# M8650D_vrs.net
KiCad netlist of a schematic drawn in EAGLE
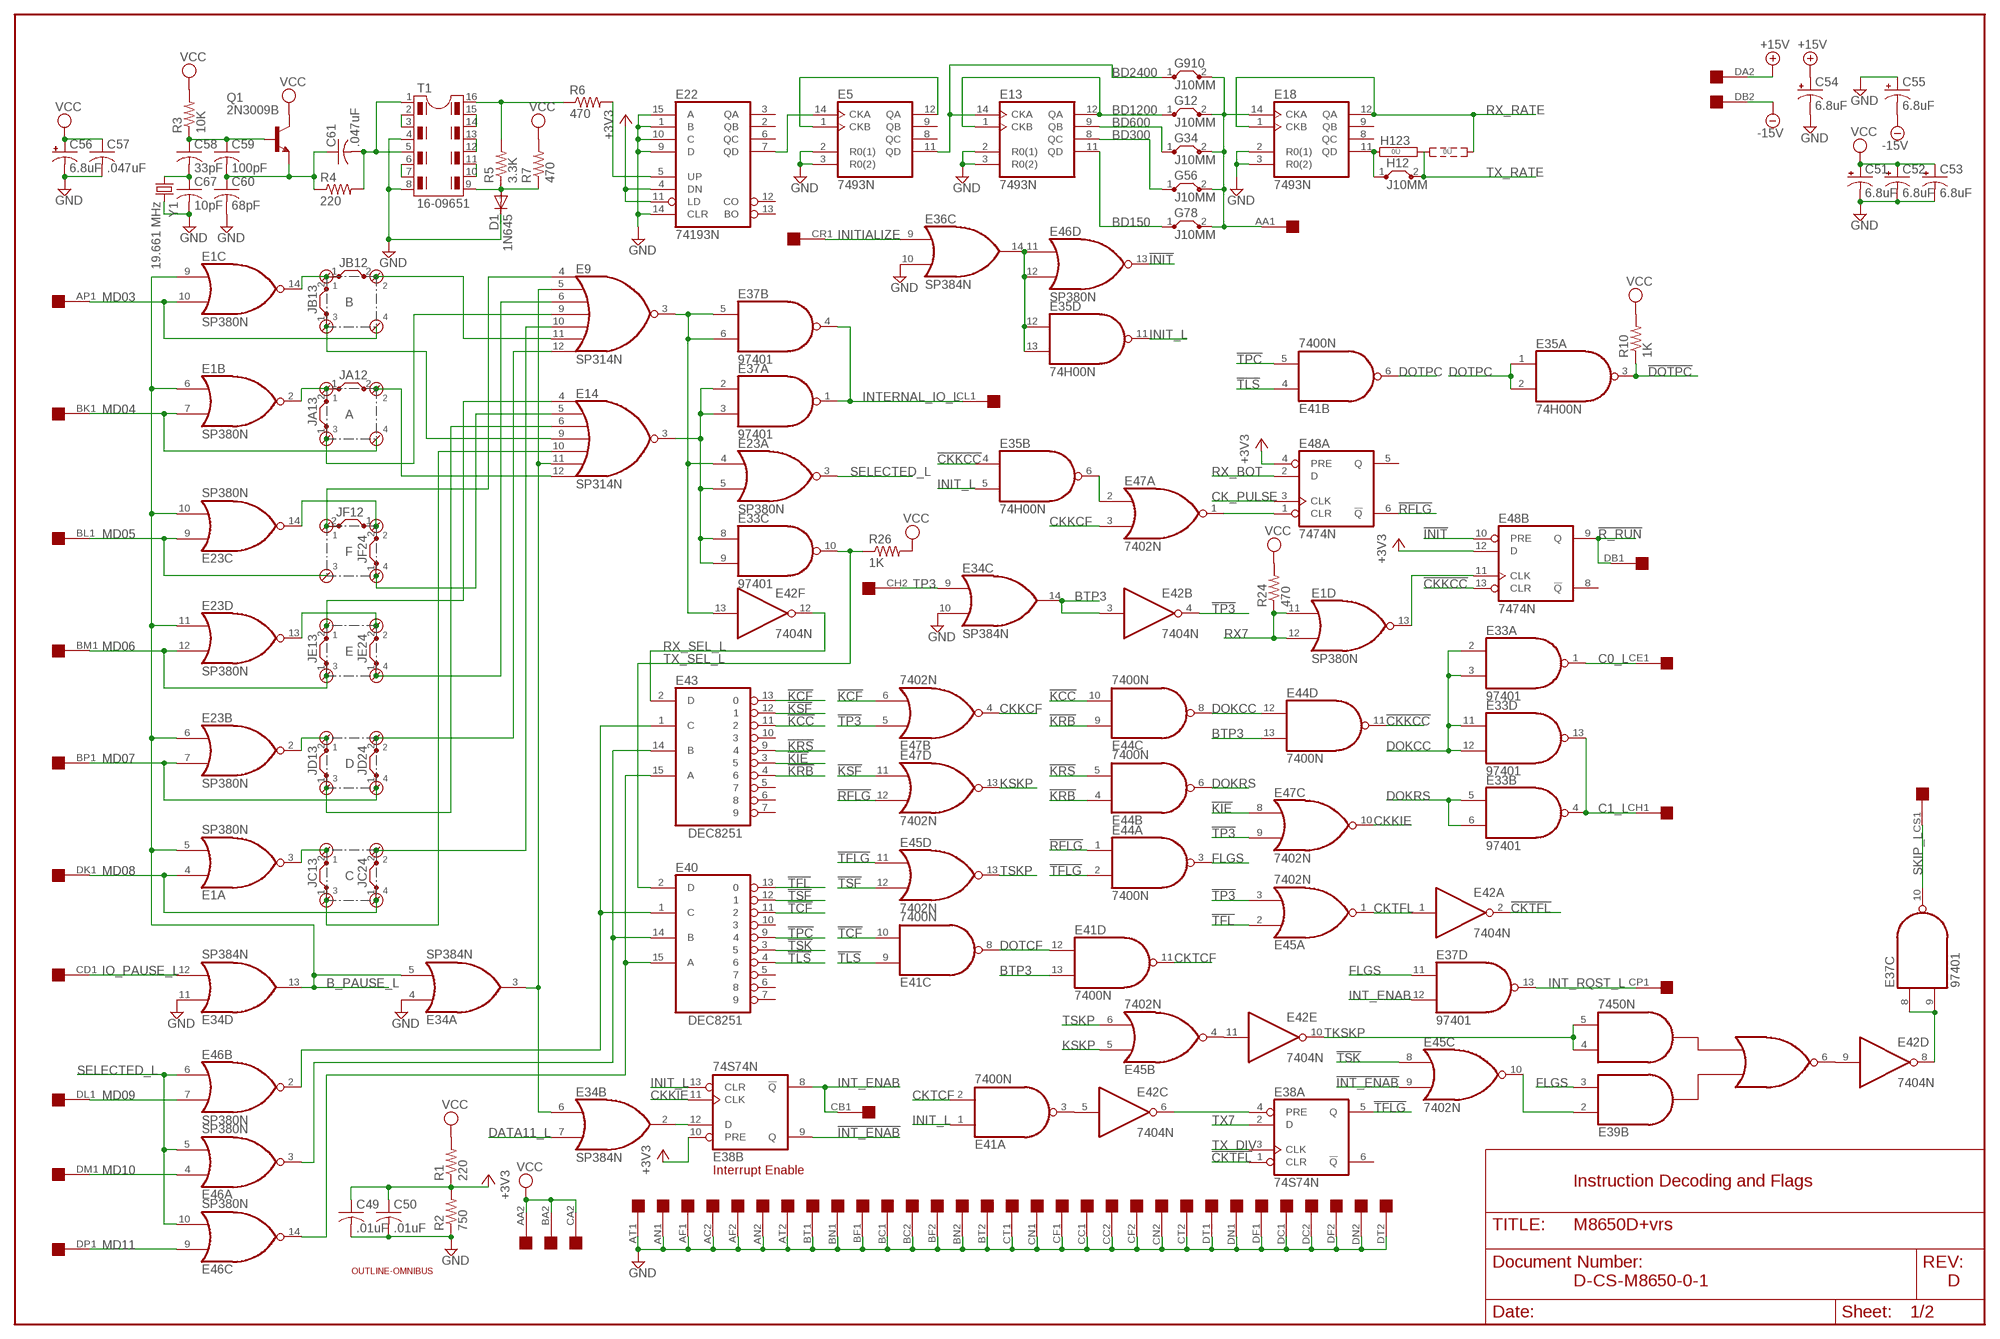
[diagram p0: schematic, sheet 1]
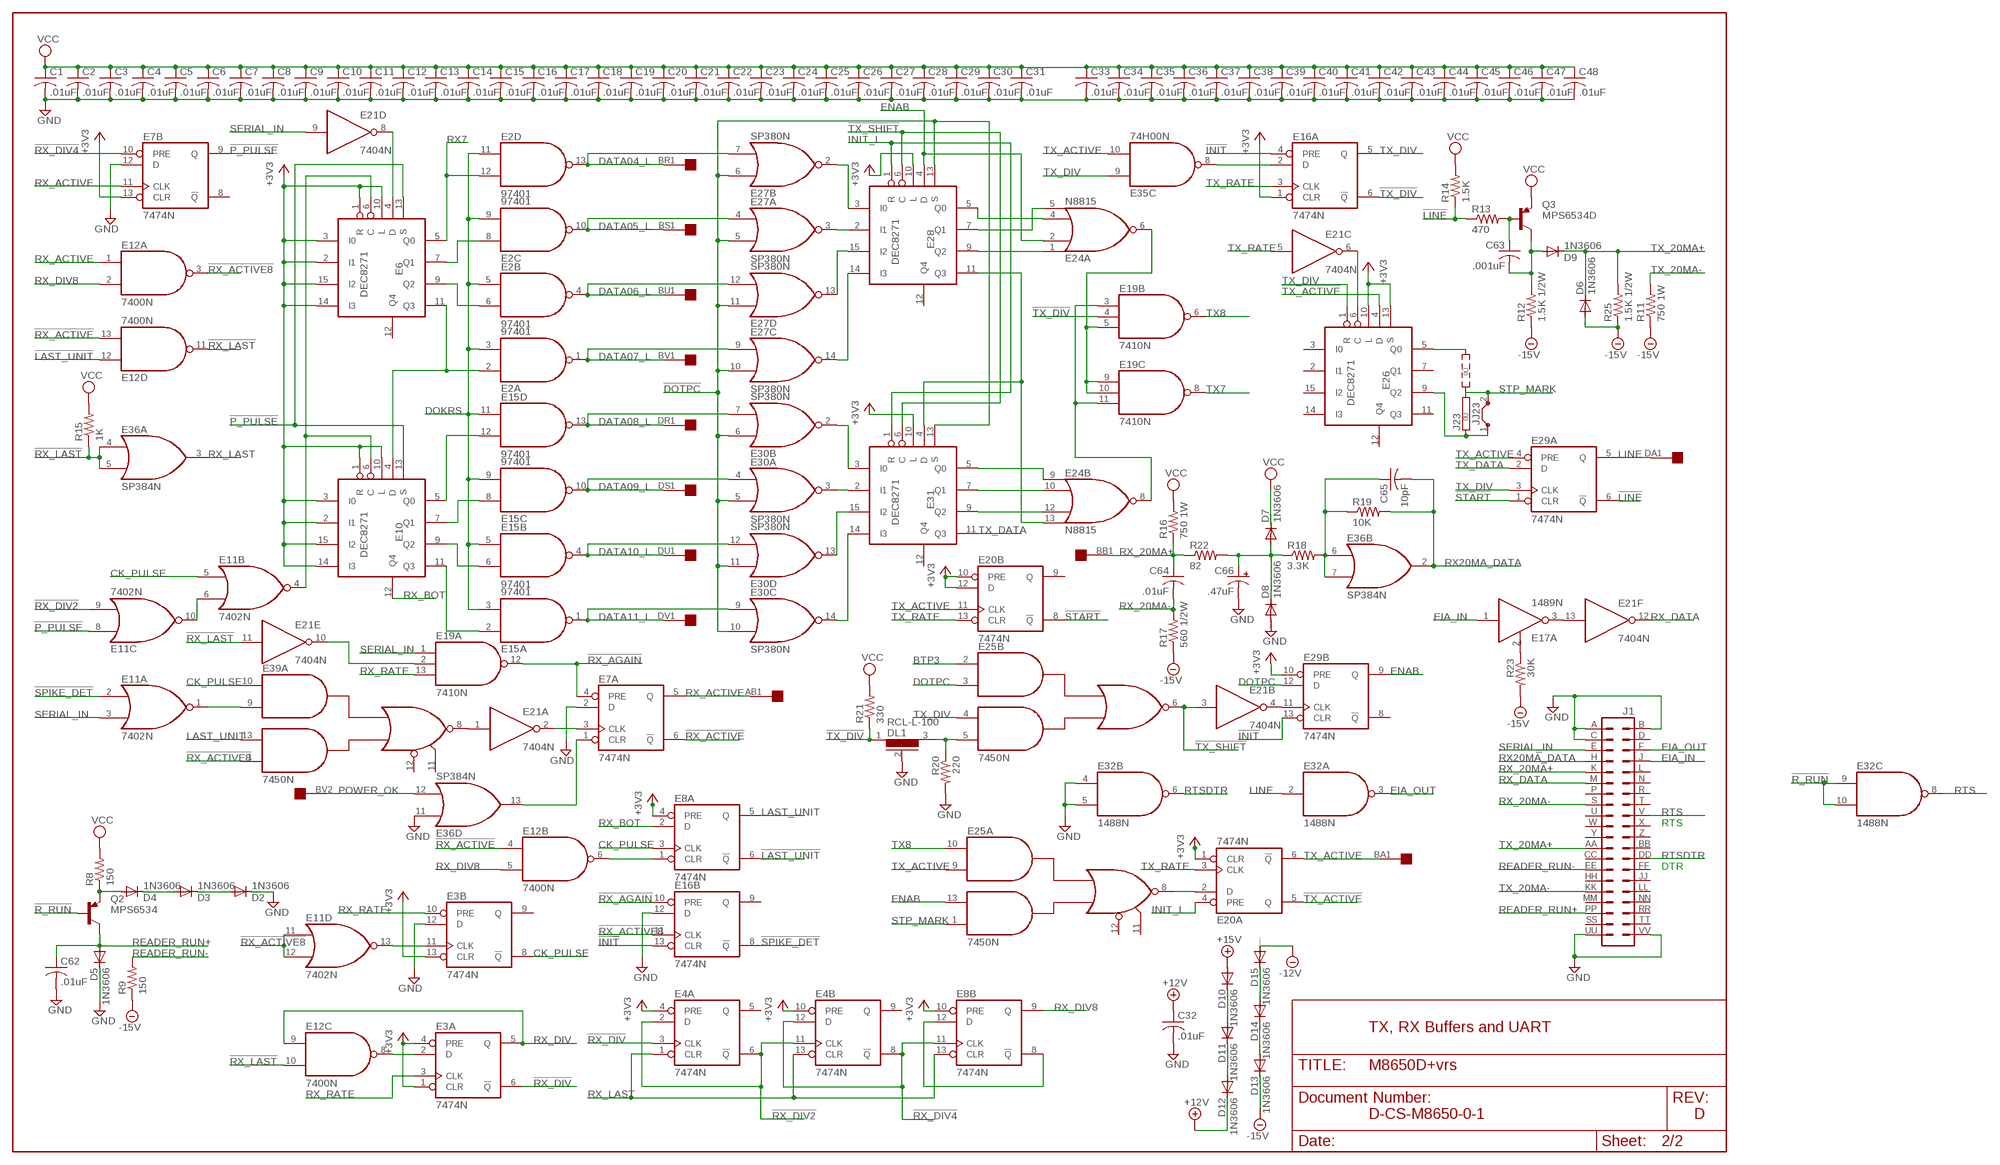
[diagram p1: schematic, sheet 2]

(export (version "E")
  (design (tool "Eeschema 10.0.6"))
  (components
    (comp (ref "C1")
      (value ".01uF")
      (footprint "eagle-import:C050-025X075")
      (libsource (lib "eagle-import") (part "C-US050-025X075"))
    )
    (comp (ref "C2")
      (value ".01uF")
      (footprint "eagle-import:C050-025X075")
      (libsource (lib "eagle-import") (part "C-US050-025X075"))
    )
    (comp (ref "C3")
      (value ".01uF")
      (footprint "eagle-import:C050-025X075")
      (libsource (lib "eagle-import") (part "C-US050-025X075"))
    )
    (comp (ref "C4")
      (value ".01uF")
      (footprint "eagle-import:C050-025X075")
      (libsource (lib "eagle-import") (part "C-US050-025X075"))
    )
    (comp (ref "C5")
      (value ".01uF")
      (footprint "eagle-import:C050-025X075")
      (libsource (lib "eagle-import") (part "C-US050-025X075"))
    )
    (comp (ref "C6")
      (value ".01uF")
      (footprint "eagle-import:C050-025X075")
      (libsource (lib "eagle-import") (part "C-US050-025X075"))
    )
    (comp (ref "C7")
      (value ".01uF")
      (footprint "eagle-import:C050-025X075")
      (libsource (lib "eagle-import") (part "C-US050-025X075"))
    )
    (comp (ref "C8")
      (value ".01uF")
      (footprint "eagle-import:C050-025X075")
      (libsource (lib "eagle-import") (part "C-US050-025X075"))
    )
    (comp (ref "C9")
      (value ".01uF")
      (footprint "eagle-import:C050-025X075")
      (libsource (lib "eagle-import") (part "C-US050-025X075"))
    )
    (comp (ref "C10")
      (value ".01uF")
      (footprint "eagle-import:C050-025X075")
      (libsource (lib "eagle-import") (part "C-US050-025X075"))
    )
    (comp (ref "C11")
      (value ".01uF")
      (footprint "eagle-import:C050-025X075")
      (libsource (lib "eagle-import") (part "C-US050-025X075"))
    )
    (comp (ref "C12")
      (value ".01uF")
      (footprint "eagle-import:C050-025X075")
      (libsource (lib "eagle-import") (part "C-US050-025X075"))
    )
    (comp (ref "C13")
      (value ".01uF")
      (footprint "eagle-import:C050-025X075")
      (libsource (lib "eagle-import") (part "C-US050-025X075"))
    )
    (comp (ref "C14")
      (value ".01uF")
      (footprint "eagle-import:C050-025X075")
      (libsource (lib "eagle-import") (part "C-US050-025X075"))
    )
    (comp (ref "C15")
      (value ".01uF")
      (footprint "eagle-import:C050-025X075")
      (libsource (lib "eagle-import") (part "C-US050-025X075"))
    )
    (comp (ref "C16")
      (value ".01uF")
      (footprint "eagle-import:C050-025X075")
      (libsource (lib "eagle-import") (part "C-US050-025X075"))
    )
    (comp (ref "C17")
      (value ".01uF")
      (footprint "eagle-import:C050-025X075")
      (libsource (lib "eagle-import") (part "C-US050-025X075"))
    )
    (comp (ref "C18")
      (value ".01uF")
      (footprint "eagle-import:C050-025X075")
      (libsource (lib "eagle-import") (part "C-US050-025X075"))
    )
    (comp (ref "C19")
      (value ".01uF")
      (footprint "eagle-import:C050-025X075")
      (libsource (lib "eagle-import") (part "C-US050-025X075"))
    )
    (comp (ref "C20")
      (value ".01uF")
      (footprint "eagle-import:C050-025X075")
      (libsource (lib "eagle-import") (part "C-US050-025X075"))
    )
    (comp (ref "C21")
      (value ".01uF")
      (footprint "eagle-import:C050-025X075")
      (libsource (lib "eagle-import") (part "C-US050-025X075"))
    )
    (comp (ref "C22")
      (value ".01uF")
      (footprint "eagle-import:C050-025X075")
      (libsource (lib "eagle-import") (part "C-US050-025X075"))
    )
    (comp (ref "C23")
      (value ".01uF")
      (footprint "eagle-import:C050-025X075")
      (libsource (lib "eagle-import") (part "C-US050-025X075"))
    )
    (comp (ref "C24")
      (value ".01uF")
      (footprint "eagle-import:C050-025X075")
      (libsource (lib "eagle-import") (part "C-US050-025X075"))
    )
    (comp (ref "C25")
      (value ".01uF")
      (footprint "eagle-import:C050-025X075")
      (libsource (lib "eagle-import") (part "C-US050-025X075"))
    )
    (comp (ref "C26")
      (value ".01uF")
      (footprint "eagle-import:C050-025X075")
      (libsource (lib "eagle-import") (part "C-US050-025X075"))
    )
    (comp (ref "C27")
      (value ".01uF")
      (footprint "eagle-import:C050-025X075")
      (libsource (lib "eagle-import") (part "C-US050-025X075"))
    )
    (comp (ref "C28")
      (value ".01uF")
      (footprint "eagle-import:C050-025X075")
      (libsource (lib "eagle-import") (part "C-US050-025X075"))
    )
    (comp (ref "C29")
      (value ".01uF")
      (footprint "eagle-import:C050-025X075")
      (libsource (lib "eagle-import") (part "C-US050-025X075"))
    )
    (comp (ref "C30")
      (value ".01uF")
      (footprint "eagle-import:C050-025X075")
      (libsource (lib "eagle-import") (part "C-US050-025X075"))
    )
    (comp (ref "C31")
      (value ".01uF")
      (footprint "eagle-import:C050-025X075")
      (libsource (lib "eagle-import") (part "C-US050-025X075"))
    )
    (comp (ref "C32")
      (value ".01uF")
      (footprint "eagle-import:C050-025X075")
      (libsource (lib "eagle-import") (part "C-US050-025X075"))
    )
    (comp (ref "C33")
      (value ".01uF")
      (footprint "eagle-import:C050-025X075")
      (libsource (lib "eagle-import") (part "C-US050-025X075"))
    )
    (comp (ref "C34")
      (value ".01uF")
      (footprint "eagle-import:C050-025X075")
      (libsource (lib "eagle-import") (part "C-US050-025X075"))
    )
    (comp (ref "C35")
      (value ".01uF")
      (footprint "eagle-import:C050-025X075")
      (libsource (lib "eagle-import") (part "C-US050-025X075"))
    )
    (comp (ref "C36")
      (value ".01uF")
      (footprint "eagle-import:C050-025X075")
      (libsource (lib "eagle-import") (part "C-US050-025X075"))
    )
    (comp (ref "C37")
      (value ".01uF")
      (footprint "eagle-import:C050-025X075")
      (libsource (lib "eagle-import") (part "C-US050-025X075"))
    )
    (comp (ref "C38")
      (value ".01uF")
      (footprint "eagle-import:C050-025X075")
      (libsource (lib "eagle-import") (part "C-US050-025X075"))
    )
    (comp (ref "C39")
      (value ".01uF")
      (footprint "eagle-import:C050-025X075")
      (libsource (lib "eagle-import") (part "C-US050-025X075"))
    )
    (comp (ref "C40")
      (value ".01uF")
      (footprint "eagle-import:C050-025X075")
      (libsource (lib "eagle-import") (part "C-US050-025X075"))
    )
    (comp (ref "C41")
      (value ".01uF")
      (footprint "eagle-import:C050-025X075")
      (libsource (lib "eagle-import") (part "C-US050-025X075"))
    )
    (comp (ref "C42")
      (value ".01uF")
      (footprint "eagle-import:C050-025X075")
      (libsource (lib "eagle-import") (part "C-US050-025X075"))
    )
    (comp (ref "C43")
      (value ".01uF")
      (footprint "eagle-import:C050-025X075")
      (libsource (lib "eagle-import") (part "C-US050-025X075"))
    )
    (comp (ref "C44")
      (value ".01uF")
      (footprint "eagle-import:C050-025X075")
      (libsource (lib "eagle-import") (part "C-US050-025X075"))
    )
    (comp (ref "C45")
      (value ".01uF")
      (footprint "eagle-import:C050-025X075")
      (libsource (lib "eagle-import") (part "C-US050-025X075"))
    )
    (comp (ref "C46")
      (value ".01uF")
      (footprint "eagle-import:C050-025X075")
      (libsource (lib "eagle-import") (part "C-US050-025X075"))
    )
    (comp (ref "C47")
      (value ".01uF")
      (footprint "eagle-import:C050-025X075")
      (libsource (lib "eagle-import") (part "C-US050-025X075"))
    )
    (comp (ref "C48")
      (value ".01uF")
      (footprint "eagle-import:C050-025X075")
      (libsource (lib "eagle-import") (part "C-US050-025X075"))
    )
    (comp (ref "C62")
      (value ".01uF")
      (footprint "eagle-import:C050-025X075")
      (libsource (lib "eagle-import") (part "C-US050-025X075"))
    )
    (comp (ref "C63")
      (value ".001uF")
      (footprint "eagle-import:C050-025X075")
      (libsource (lib "eagle-import") (part "C-US050-025X075"))
    )
    (comp (ref "C64")
      (value ".01uF")
      (footprint "eagle-import:C050-025X075")
      (libsource (lib "eagle-import") (part "C-US050-025X075"))
    )
    (comp (ref "C65")
      (value "10pF")
      (footprint "eagle-import:C050-025X075")
      (libsource (lib "eagle-import") (part "C-US050-025X075"))
    )
    (comp (ref "C66")
      (value ".47uF")
      (footprint "eagle-import:E15-5")
      (libsource (lib "eagle-import") (part "CPOL-USE15-5AXIAL"))
    )
    (comp (ref "D2")
      (value "1N3606")
      (footprint "eagle-import:DO35-10")
      (libsource (lib "eagle-import") (part "DIODE-DO35-10"))
    )
    (comp (ref "D3")
      (value "1N3606")
      (footprint "eagle-import:DO35-10")
      (libsource (lib "eagle-import") (part "DIODE-DO35-10"))
    )
    (comp (ref "D4")
      (value "1N3606")
      (footprint "eagle-import:DO35-10")
      (libsource (lib "eagle-import") (part "DIODE-DO35-10"))
    )
    (comp (ref "D5")
      (value "1N3606")
      (footprint "eagle-import:DO35-10")
      (libsource (lib "eagle-import") (part "DIODE-DO35-10"))
    )
    (comp (ref "D6")
      (value "1N3606")
      (footprint "eagle-import:DO35-10")
      (libsource (lib "eagle-import") (part "DIODE-DO35-10"))
    )
    (comp (ref "D7")
      (value "1N3606")
      (footprint "eagle-import:DO35-10")
      (libsource (lib "eagle-import") (part "DIODE-DO35-10"))
    )
    (comp (ref "D8")
      (value "1N3606")
      (footprint "eagle-import:DO35-10")
      (libsource (lib "eagle-import") (part "DIODE-DO35-10"))
    )
    (comp (ref "D9")
      (value "1N3606")
      (footprint "eagle-import:DO35-10")
      (libsource (lib "eagle-import") (part "DIODE-DO35-10"))
    )
    (comp (ref "D10")
      (value "1N3606")
      (footprint "eagle-import:DO35-10")
      (libsource (lib "eagle-import") (part "DIODE-DO35-10"))
    )
    (comp (ref "D11")
      (value "1N3606")
      (footprint "eagle-import:DO35-10")
      (libsource (lib "eagle-import") (part "DIODE-DO35-10"))
    )
    (comp (ref "D12")
      (value "1N3606")
      (footprint "eagle-import:DO35-10")
      (libsource (lib "eagle-import") (part "DIODE-DO35-10"))
    )
    (comp (ref "D13")
      (value "1N3606")
      (footprint "eagle-import:DO35-10")
      (libsource (lib "eagle-import") (part "DIODE-DO35-10"))
    )
    (comp (ref "D14")
      (value "1N3606")
      (footprint "eagle-import:DO35-10")
      (libsource (lib "eagle-import") (part "DIODE-DO35-10"))
    )
    (comp (ref "D15")
      (value "1N3606")
      (footprint "eagle-import:DO35-10")
      (libsource (lib "eagle-import") (part "DIODE-DO35-10"))
    )
    (comp (ref "DL1")
      (value "RCL-L-100")
      (footprint "eagle-import:RCL-L-00-05")
      (libsource (lib "eagle-import") (part "RCL-L-00-05"))
    )
    (comp (ref "E2")
      (value "97401")
      (footprint "eagle-import:DIL14")
      (libsource (lib "eagle-import") (part "7401NLS"))
    )
    (comp (ref "E3")
      (value "7474N")
      (footprint "eagle-import:DIL14")
      (libsource (lib "eagle-import") (part "7474NS"))
    )
    (comp (ref "E4")
      (value "7474N")
      (footprint "eagle-import:DIL14")
      (libsource (lib "eagle-import") (part "7474NS"))
    )
    (comp (ref "E6")
      (value "DEC8271")
      (footprint "eagle-import:DIL16")
      (libsource (lib "eagle-import") (part "DEC8271"))
    )
    (comp (ref "E7")
      (value "7474N")
      (footprint "eagle-import:DIL14")
      (libsource (lib "eagle-import") (part "7474NS"))
    )
    (comp (ref "E8")
      (value "7474N")
      (footprint "eagle-import:DIL14")
      (libsource (lib "eagle-import") (part "7474NS"))
    )
    (comp (ref "E10")
      (value "DEC8271")
      (footprint "eagle-import:DIL16")
      (libsource (lib "eagle-import") (part "DEC8271"))
    )
    (comp (ref "E11")
      (value "7402N")
      (footprint "eagle-import:DIL14")
      (libsource (lib "eagle-import") (part "7402N"))
    )
    (comp (ref "E12")
      (value "7400N")
      (footprint "eagle-import:DIL14")
      (libsource (lib "eagle-import") (part "7400N"))
    )
    (comp (ref "E15")
      (value "97401")
      (footprint "eagle-import:DIL14")
      (libsource (lib "eagle-import") (part "7401NLS"))
    )
    (comp (ref "E16")
      (value "7474N")
      (footprint "eagle-import:DIL14")
      (libsource (lib "eagle-import") (part "7474NS"))
    )
    (comp (ref "E17")
      (value "1489N")
      (footprint "eagle-import:DIL14")
      (libsource (lib "eagle-import") (part "1489N"))
    )
    (comp (ref "E19")
      (value "7410N")
      (footprint "eagle-import:DIL14")
      (libsource (lib "eagle-import") (part "7410N"))
    )
    (comp (ref "E20")
      (value "7474N")
      (footprint "eagle-import:DIL14")
      (libsource (lib "eagle-import") (part "7474NS"))
    )
    (comp (ref "E21")
      (value "7404N")
      (footprint "eagle-import:DIL14")
      (libsource (lib "eagle-import") (part "7404N"))
    )
    (comp (ref "E24")
      (value "N8815")
      (footprint "eagle-import:DIL14")
      (libsource (lib "eagle-import") (part "N8815"))
    )
    (comp (ref "E25")
      (value "7450N")
      (footprint "eagle-import:DIL14")
      (libsource (lib "eagle-import") (part "7450N"))
    )
    (comp (ref "E26")
      (value "DEC8271")
      (footprint "eagle-import:DIL16")
      (libsource (lib "eagle-import") (part "DEC8271"))
    )
    (comp (ref "E27")
      (value "SP380N")
      (footprint "eagle-import:DIL14")
      (libsource (lib "eagle-import") (part "SP380N"))
    )
    (comp (ref "E28")
      (value "DEC8271")
      (footprint "eagle-import:DIL16")
      (libsource (lib "eagle-import") (part "DEC8271"))
    )
    (comp (ref "E29")
      (value "7474N")
      (footprint "eagle-import:DIL14")
      (libsource (lib "eagle-import") (part "7474NS"))
    )
    (comp (ref "E30")
      (value "SP380N")
      (footprint "eagle-import:DIL14")
      (libsource (lib "eagle-import") (part "SP380N"))
    )
    (comp (ref "E31")
      (value "DEC8271")
      (footprint "eagle-import:DIL16")
      (libsource (lib "eagle-import") (part "DEC8271"))
    )
    (comp (ref "E32")
      (value "1488N")
      (footprint "eagle-import:DIL14")
      (libsource (lib "eagle-import") (part "1488N"))
    )
    (comp (ref "E35")
      (value "74H00N")
      (footprint "eagle-import:DIL14")
      (libsource (lib "eagle-import") (part "7400N"))
    )
    (comp (ref "E36")
      (value "SP384N")
      (footprint "eagle-import:DIL14")
      (libsource (lib "eagle-import") (part "SP384N"))
    )
    (comp (ref "E39")
      (value "7450N")
      (footprint "eagle-import:DIL14")
      (libsource (lib "eagle-import") (part "7450N"))
    )
    (comp (ref "J1")
      (value "DEC40PINH")
      (footprint "eagle-import:DEC40PINH")
      (libsource (lib "eagle-import") (part "DEC40PINH"))
    )
    (comp (ref "J23")
      (value "0R2")
      (footprint "eagle-import:0R2_10")
      (libsource (lib "eagle-import") (part "0R2"))
    )
    (comp (ref "JJ23")
      (value "J10MM")
      (footprint "eagle-import:10")
      (libsource (lib "eagle-import") (part "J10MM"))
    )
    (comp (ref "Q2")
      (value "MPS6534")
      (footprint "eagle-import:TO5")
      (libsource (lib "eagle-import") (part "-PNP-TO5"))
    )
    (comp (ref "Q3")
      (value "MPS6534D")
      (footprint "eagle-import:TO5")
      (libsource (lib "eagle-import") (part "-PNP-TO5"))
    )
    (comp (ref "R8")
      (value "150")
      (footprint "eagle-import:0207_10")
      (libsource (lib "eagle-import") (part "R-US_0207/10"))
    )
    (comp (ref "R9")
      (value "150")
      (footprint "eagle-import:0207_10")
      (libsource (lib "eagle-import") (part "R-US_0207/10"))
    )
    (comp (ref "R11")
      (value "750 1W")
      (footprint "eagle-import:0617_17")
      (libsource (lib "eagle-import") (part "R-US_0617/17"))
    )
    (comp (ref "R12")
      (value "1.5K 1/2W")
      (footprint "eagle-import:0411_15")
      (libsource (lib "eagle-import") (part "R-US_0411/15"))
    )
    (comp (ref "R13")
      (value "470")
      (footprint "eagle-import:0207_10")
      (libsource (lib "eagle-import") (part "R-US_0207/10"))
    )
    (comp (ref "R14")
      (value "1.5K")
      (footprint "eagle-import:0207_10")
      (libsource (lib "eagle-import") (part "R-US_0207/10"))
    )
    (comp (ref "R15")
      (value "1K")
      (footprint "eagle-import:0207_10")
      (libsource (lib "eagle-import") (part "R-US_0207/10"))
    )
    (comp (ref "R16")
      (value "750 1W")
      (footprint "eagle-import:0617_17")
      (libsource (lib "eagle-import") (part "R-US_0617/17"))
    )
    (comp (ref "R17")
      (value "560 1/2W")
      (footprint "eagle-import:0411_15")
      (libsource (lib "eagle-import") (part "R-US_0411/15"))
    )
    (comp (ref "R18")
      (value "3.3K")
      (footprint "eagle-import:0207_10")
      (libsource (lib "eagle-import") (part "R-US_0207/10"))
    )
    (comp (ref "R19")
      (value "10K")
      (footprint "eagle-import:0207_10")
      (libsource (lib "eagle-import") (part "R-US_0207/10"))
    )
    (comp (ref "R20")
      (value "220")
      (footprint "eagle-import:0207_10")
      (libsource (lib "eagle-import") (part "R-US_0207/10"))
    )
    (comp (ref "R21")
      (value "330")
      (footprint "eagle-import:0207_10")
      (libsource (lib "eagle-import") (part "R-US_0207/10"))
    )
    (comp (ref "R22")
      (value "82")
      (footprint "eagle-import:0207_10")
      (libsource (lib "eagle-import") (part "R-US_0207/10"))
    )
    (comp (ref "R23")
      (value "30K")
      (footprint "eagle-import:0207_10")
      (libsource (lib "eagle-import") (part "R-US_0207/10"))
    )
    (comp (ref "R25")
      (value "1.5K 1/2W")
      (footprint "eagle-import:0411_15")
      (libsource (lib "eagle-import") (part "R-US_0411/15"))
    )
    (comp (ref "U$2")
      (value "QUAD")
      (footprint "eagle-import:EDGE-CON8")
      (libsource (lib "eagle-import") (part "QUAD"))
    )
    (comp (ref "A")
      (value "JUMPER4")
      (footprint "eagle-import:JUMPER4")
      (libsource (lib "eagle-import") (part "JUMPER4"))
    )
    (comp (ref "B")
      (value "JUMPER4")
      (footprint "eagle-import:JUMPER4")
      (libsource (lib "eagle-import") (part "JUMPER4"))
    )
    (comp (ref "C")
      (value "JUMPER4")
      (footprint "eagle-import:JUMPER4")
      (libsource (lib "eagle-import") (part "JUMPER4"))
    )
    (comp (ref "C49")
      (value ".01uF")
      (footprint "eagle-import:C050-025X075")
      (libsource (lib "eagle-import") (part "C-US050-025X075"))
    )
    (comp (ref "C50")
      (value ".01uF")
      (footprint "eagle-import:C050-025X075")
      (libsource (lib "eagle-import") (part "C-US050-025X075"))
    )
    (comp (ref "C51")
      (value "6.8uF")
      (footprint "eagle-import:E12-8")
      (libsource (lib "eagle-import") (part "CPOL-USE20-8AXIAL"))
    )
    (comp (ref "C52")
      (value "6.8uF")
      (footprint "eagle-import:E12-8")
      (libsource (lib "eagle-import") (part "CPOL-USE20-8AXIAL"))
    )
    (comp (ref "C53")
      (value "6.8uF")
      (footprint "eagle-import:E12-8")
      (libsource (lib "eagle-import") (part "CPOL-USE20-8AXIAL"))
    )
    (comp (ref "C54")
      (value "6.8uF")
      (footprint "eagle-import:E12-8")
      (libsource (lib "eagle-import") (part "CPOL-USE20-8AXIAL"))
    )
    (comp (ref "C55")
      (value "6.8uF")
      (footprint "eagle-import:E12-8")
      (libsource (lib "eagle-import") (part "CPOL-USE20-8AXIAL"))
    )
    (comp (ref "C56")
      (value "6.8uF")
      (footprint "eagle-import:E12-8")
      (libsource (lib "eagle-import") (part "CPOL-USE20-8AXIAL"))
    )
    (comp (ref "C57")
      (value ".047uF")
      (footprint "eagle-import:C050-025X075")
      (libsource (lib "eagle-import") (part "C-US050-025X075"))
    )
    (comp (ref "C58")
      (value "33pF")
      (footprint "eagle-import:C050-025X075")
      (libsource (lib "eagle-import") (part "C-US050-025X075"))
    )
    (comp (ref "C59")
      (value "100pF")
      (footprint "eagle-import:C050-025X075")
      (libsource (lib "eagle-import") (part "C-US050-025X075"))
    )
    (comp (ref "C60")
      (value "68pF")
      (footprint "eagle-import:C050-025X075")
      (libsource (lib "eagle-import") (part "C-US050-025X075"))
    )
    (comp (ref "C61")
      (value ".047uF")
      (footprint "eagle-import:C050-025X075")
      (libsource (lib "eagle-import") (part "C-US050-025X075"))
    )
    (comp (ref "C67")
      (value "10pF")
      (footprint "eagle-import:C050-025X075")
      (libsource (lib "eagle-import") (part "C-US050-025X075"))
    )
    (comp (ref "D")
      (value "JUMPER4")
      (footprint "eagle-import:JUMPER4")
      (libsource (lib "eagle-import") (part "JUMPER4"))
    )
    (comp (ref "D1")
      (value "1N645")
      (footprint "eagle-import:DO35-10")
      (libsource (lib "eagle-import") (part "DIODE-DO35-10"))
    )
    (comp (ref "E")
      (value "JUMPER4")
      (footprint "eagle-import:JUMPER4")
      (libsource (lib "eagle-import") (part "JUMPER4"))
    )
    (comp (ref "E1")
      (value "SP380N")
      (footprint "eagle-import:DIL14")
      (libsource (lib "eagle-import") (part "SP380N"))
    )
    (comp (ref "E5")
      (value "7493N")
      (footprint "eagle-import:DIL14")
      (libsource (lib "eagle-import") (part "7493NLS"))
    )
    (comp (ref "E9")
      (value "SP314N")
      (footprint "eagle-import:DIL14")
      (libsource (lib "eagle-import") (part "SP314N"))
    )
    (comp (ref "E13")
      (value "7493N")
      (footprint "eagle-import:DIL14")
      (libsource (lib "eagle-import") (part "7493NLS"))
    )
    (comp (ref "E14")
      (value "SP314N")
      (footprint "eagle-import:DIL14")
      (libsource (lib "eagle-import") (part "SP314N"))
    )
    (comp (ref "E18")
      (value "7493N")
      (footprint "eagle-import:DIL14")
      (libsource (lib "eagle-import") (part "7493NLS"))
    )
    (comp (ref "E22")
      (value "74193N")
      (footprint "eagle-import:DIL16")
      (libsource (lib "eagle-import") (part "74193N"))
    )
    (comp (ref "E23")
      (value "SP380N")
      (footprint "eagle-import:DIL14")
      (libsource (lib "eagle-import") (part "SP380N"))
    )
    (comp (ref "E33")
      (value "97401")
      (footprint "eagle-import:DIL14")
      (libsource (lib "eagle-import") (part "7401NLS"))
    )
    (comp (ref "E34")
      (value "SP384N")
      (footprint "eagle-import:DIL14")
      (libsource (lib "eagle-import") (part "SP384N"))
    )
    (comp (ref "E37")
      (value "97401")
      (footprint "eagle-import:DIL14")
      (libsource (lib "eagle-import") (part "7401NLS"))
    )
    (comp (ref "E38")
      (value "74S74N")
      (footprint "eagle-import:DIL14")
      (libsource (lib "eagle-import") (part "7474NS"))
    )
    (comp (ref "E40")
      (value "DEC8251")
      (footprint "eagle-import:DIL16")
      (libsource (lib "eagle-import") (part "DEC8251"))
    )
    (comp (ref "E41")
      (value "7400N")
      (footprint "eagle-import:DIL14")
      (libsource (lib "eagle-import") (part "7400N"))
    )
    (comp (ref "E42")
      (value "7404N")
      (footprint "eagle-import:DIL14")
      (libsource (lib "eagle-import") (part "7404N"))
    )
    (comp (ref "E43")
      (value "DEC8251")
      (footprint "eagle-import:DIL16")
      (libsource (lib "eagle-import") (part "DEC8251"))
    )
    (comp (ref "E44")
      (value "7400N")
      (footprint "eagle-import:DIL14")
      (libsource (lib "eagle-import") (part "7400N"))
    )
    (comp (ref "E45")
      (value "7402N")
      (footprint "eagle-import:DIL14")
      (libsource (lib "eagle-import") (part "7402N"))
    )
    (comp (ref "E46")
      (value "SP380N")
      (footprint "eagle-import:DIL14")
      (libsource (lib "eagle-import") (part "SP380N"))
    )
    (comp (ref "E47")
      (value "7402N")
      (footprint "eagle-import:DIL14")
      (libsource (lib "eagle-import") (part "7402N"))
    )
    (comp (ref "E48")
      (value "7474N")
      (footprint "eagle-import:DIL14")
      (libsource (lib "eagle-import") (part "7474NS"))
    )
    (comp (ref "F")
      (value "JUMPER4")
      (footprint "eagle-import:JUMPER4")
      (libsource (lib "eagle-import") (part "JUMPER4"))
    )
    (comp (ref "G12")
      (value "J10MM")
      (footprint "eagle-import:10")
      (libsource (lib "eagle-import") (part "J10MM"))
    )
    (comp (ref "G34")
      (value "J10MM")
      (footprint "eagle-import:10")
      (libsource (lib "eagle-import") (part "J10MM"))
    )
    (comp (ref "G56")
      (value "J10MM")
      (footprint "eagle-import:10")
      (libsource (lib "eagle-import") (part "J10MM"))
    )
    (comp (ref "G78")
      (value "J10MM")
      (footprint "eagle-import:10")
      (libsource (lib "eagle-import") (part "J10MM"))
    )
    (comp (ref "G910")
      (value "J10MM")
      (footprint "eagle-import:10")
      (libsource (lib "eagle-import") (part "J10MM"))
    )
    (comp (ref "H12")
      (value "J10MM")
      (footprint "eagle-import:10")
      (libsource (lib "eagle-import") (part "J10MM"))
    )
    (comp (ref "H123")
      (value "0R2")
      (footprint "eagle-import:0R2_10")
      (libsource (lib "eagle-import") (part "0R2"))
    )
    (comp (ref "JA12")
      (value "J10MM")
      (footprint "eagle-import:10")
      (libsource (lib "eagle-import") (part "J10MM"))
    )
    (comp (ref "JA13")
      (value "J10MM")
      (footprint "eagle-import:10")
      (libsource (lib "eagle-import") (part "J10MM"))
    )
    (comp (ref "JB12")
      (value "J10MM")
      (footprint "eagle-import:10")
      (libsource (lib "eagle-import") (part "J10MM"))
    )
    (comp (ref "JB13")
      (value "J10MM")
      (footprint "eagle-import:10")
      (libsource (lib "eagle-import") (part "J10MM"))
    )
    (comp (ref "JC13")
      (value "J10MM")
      (footprint "eagle-import:10")
      (libsource (lib "eagle-import") (part "J10MM"))
    )
    (comp (ref "JC24")
      (value "J10MM")
      (footprint "eagle-import:10")
      (libsource (lib "eagle-import") (part "J10MM"))
    )
    (comp (ref "JD13")
      (value "J10MM")
      (footprint "eagle-import:10")
      (libsource (lib "eagle-import") (part "J10MM"))
    )
    (comp (ref "JD24")
      (value "J10MM")
      (footprint "eagle-import:10")
      (libsource (lib "eagle-import") (part "J10MM"))
    )
    (comp (ref "JE13")
      (value "J10MM")
      (footprint "eagle-import:10")
      (libsource (lib "eagle-import") (part "J10MM"))
    )
    (comp (ref "JE24")
      (value "J10MM")
      (footprint "eagle-import:10")
      (libsource (lib "eagle-import") (part "J10MM"))
    )
    (comp (ref "JF12")
      (value "J10MM")
      (footprint "eagle-import:10")
      (libsource (lib "eagle-import") (part "J10MM"))
    )
    (comp (ref "JF24")
      (value "J10MM")
      (footprint "eagle-import:10")
      (libsource (lib "eagle-import") (part "J10MM"))
    )
    (comp (ref "Q1")
      (value "2N3009B")
      (footprint "eagle-import:TO5")
      (libsource (lib "eagle-import") (part "-NPN-TO5"))
    )
    (comp (ref "R1")
      (value "220")
      (footprint "eagle-import:0207_10")
      (libsource (lib "eagle-import") (part "R-US_0207/10"))
    )
    (comp (ref "R2")
      (value "750")
      (footprint "eagle-import:0207_10")
      (libsource (lib "eagle-import") (part "R-US_0207/10"))
    )
    (comp (ref "R3")
      (value "10K")
      (footprint "eagle-import:0207_10")
      (libsource (lib "eagle-import") (part "R-US_0207/10"))
    )
    (comp (ref "R4")
      (value "220")
      (footprint "eagle-import:0207_10")
      (libsource (lib "eagle-import") (part "R-US_0207/10"))
    )
    (comp (ref "R5")
      (value "3.3K")
      (footprint "eagle-import:0207_10")
      (libsource (lib "eagle-import") (part "R-US_0207/10"))
    )
    (comp (ref "R6")
      (value "470")
      (footprint "eagle-import:0207_10")
      (libsource (lib "eagle-import") (part "R-US_0207/10"))
    )
    (comp (ref "R7")
      (value "470")
      (footprint "eagle-import:0207_10")
      (libsource (lib "eagle-import") (part "R-US_0207/10"))
    )
    (comp (ref "R10")
      (value "1K")
      (footprint "eagle-import:0207_10")
      (libsource (lib "eagle-import") (part "R-US_0207/10"))
    )
    (comp (ref "R24")
      (value "470")
      (footprint "eagle-import:0207_10")
      (libsource (lib "eagle-import") (part "R-US_0207/10"))
    )
    (comp (ref "R26")
      (value "1K")
      (footprint "eagle-import:0207_10")
      (libsource (lib "eagle-import") (part "R-US_0207/10"))
    )
    (comp (ref "T1")
      (value "16-09651")
      (footprint "eagle-import:DIL16")
      (libsource (lib "eagle-import") (part "DIL16"))
    )
    (comp (ref "U$1")
      (value "OUTLINE-OMNIBUS")
      (footprint "eagle-import:OMNIBUS")
      (libsource (lib "eagle-import") (part "OUTLINE-OMNIBUS"))
    )
    (comp (ref "Y1")
      (value "19.661 MHz")
      (footprint "eagle-import:HC49TL-H")
      (libsource (lib "eagle-import") (part "CRYSTALHC49TL-H"))
    )
  )
  (nets
    (net (code "1") (name "+3V3") (class "Default")
      (node (ref "C49") (pin "1") (pinfunction "1_1") (pintype "passive"))
      (node (ref "C50") (pin "1") (pinfunction "1_1") (pintype "passive"))
      (node (ref "E10") (pin "1") (pinfunction "R_1") (pintype "input"))
      (node (ref "E10") (pin "10") (pinfunction "L_10") (pintype "input"))
      (node (ref "E10") (pin "14") (pinfunction "I3_14") (pintype "input"))
      (node (ref "E10") (pin "15") (pinfunction "I2_15") (pintype "input"))
      (node (ref "E10") (pin "2") (pinfunction "I1_2") (pintype "input"))
      (node (ref "E10") (pin "3") (pinfunction "I0_3") (pintype "input"))
      (node (ref "E16") (pin "1") (pinfunction "CLR_1") (pintype "input"))
      (node (ref "E20") (pin "1") (pinfunction "CLR_1") (pintype "input"))
      (node (ref "E20") (pin "10") (pinfunction "PRE_10") (pintype "input"))
      (node (ref "E20") (pin "12") (pinfunction "D_12") (pintype "input"))
      (node (ref "E22") (pin "11") (pinfunction "LD_11") (pintype "input"))
      (node (ref "E22") (pin "4") (pinfunction "DN_4") (pintype "input"))
      (node (ref "E26") (pin "10") (pinfunction "L_10") (pintype "input"))
      (node (ref "E26") (pin "13") (pinfunction "S_13") (pintype "input"))
      (node (ref "E28") (pin "10") (pinfunction "L_10") (pintype "input"))
      (node (ref "E29") (pin "10") (pinfunction "PRE_10") (pintype "input"))
      (node (ref "E3") (pin "1") (pinfunction "CLR_1") (pintype "input"))
      (node (ref "E3") (pin "13") (pinfunction "CLR_13") (pintype "input"))
      (node (ref "E3") (pin "4") (pinfunction "PRE_4") (pintype "input"))
      (node (ref "E31") (pin "10") (pinfunction "L_10") (pintype "input"))
      (node (ref "E38") (pin "10") (pinfunction "PRE_10") (pintype "input"))
      (node (ref "E4") (pin "10") (pinfunction "PRE_10") (pintype "input"))
      (node (ref "E4") (pin "4") (pinfunction "PRE_4") (pintype "input"))
      (node (ref "E48") (pin "12") (pinfunction "D_12") (pintype "input"))
      (node (ref "E48") (pin "4") (pinfunction "PRE_4") (pintype "input"))
      (node (ref "E6") (pin "1") (pinfunction "R_1") (pintype "input"))
      (node (ref "E6") (pin "10") (pinfunction "L_10") (pintype "input"))
      (node (ref "E6") (pin "14") (pinfunction "I3_14") (pintype "input"))
      (node (ref "E6") (pin "15") (pinfunction "I2_15") (pintype "input"))
      (node (ref "E6") (pin "2") (pinfunction "I1_2") (pintype "input"))
      (node (ref "E6") (pin "3") (pinfunction "I0_3") (pintype "input"))
      (node (ref "E7") (pin "13") (pinfunction "CLR_13") (pintype "input"))
      (node (ref "E8") (pin "10") (pinfunction "PRE_10") (pintype "input"))
      (node (ref "E8") (pin "4") (pinfunction "PRE_4") (pintype "input"))
      (node (ref "R1") (pin "1") (pinfunction "1_1") (pintype "passive"))
      (node (ref "R2") (pin "2") (pinfunction "2_2") (pintype "passive"))
    )
    (net (code "2") (name "+12V") (class "Default")
      (node (ref "C32") (pin "1") (pinfunction "1_1") (pintype "passive"))
      (node (ref "D12") (pin "C") (pinfunction "C_C") (pintype "passive"))
    )
    (net (code "3") (name "+15V") (class "Default")
      (node (ref "C54") (pin "+") (pinfunction "+_+") (pintype "passive"))
      (node (ref "D10") (pin "A") (pinfunction "A_A") (pintype "passive"))
      (node (ref "U$2") (pin "DA2") (pinfunction "1_DA2") (pintype "bidirectional"))
    )
    (net (code "4") (name "-12V") (class "Default")
      (node (ref "D15") (pin "A") (pinfunction "A_A") (pintype "passive"))
    )
    (net (code "5") (name "-15V") (class "Default")
      (node (ref "C55") (pin "-") (pinfunction "-_-") (pintype "passive"))
      (node (ref "D13") (pin "C") (pinfunction "C_C") (pintype "passive"))
      (node (ref "D6") (pin "A") (pinfunction "A_A") (pintype "passive"))
      (node (ref "R11") (pin "1") (pinfunction "1_1") (pintype "passive"))
      (node (ref "R12") (pin "1") (pinfunction "1_1") (pintype "passive"))
      (node (ref "R17") (pin "1") (pinfunction "1_1") (pintype "passive"))
      (node (ref "R23") (pin "2") (pinfunction "2_2") (pintype "passive"))
      (node (ref "R25") (pin "1") (pinfunction "1_1") (pintype "passive"))
      (node (ref "R9") (pin "1") (pinfunction "1_1") (pintype "passive"))
      (node (ref "U$2") (pin "DB2") (pinfunction "1_DB2") (pintype "bidirectional"))
    )
    (net (code "6") (name "BD150") (class "Default")
      (node (ref "E13") (pin "11") (pinfunction "QD_11") (pintype "output"))
      (node (ref "G78") (pin "1") (pinfunction "1_1") (pintype "passive"))
    )
    (net (code "7") (name "BD300") (class "Default")
      (node (ref "E13") (pin "8") (pinfunction "QC_8") (pintype "output"))
      (node (ref "G56") (pin "1") (pinfunction "1_1") (pintype "passive"))
    )
    (net (code "8") (name "BD600") (class "Default")
      (node (ref "E13") (pin "9") (pinfunction "QB_9") (pintype "output"))
      (node (ref "G34") (pin "1") (pinfunction "1_1") (pintype "passive"))
    )
    (net (code "9") (name "BD1200") (class "Default")
      (node (ref "E13") (pin "1") (pinfunction "CKB_1") (pintype "input"))
      (node (ref "E13") (pin "12") (pinfunction "QA_12") (pintype "output"))
      (node (ref "G12") (pin "1") (pinfunction "1_1") (pintype "passive"))
    )
    (net (code "10") (name "BD2400") (class "Default")
      (node (ref "E13") (pin "14") (pinfunction "CKA_14") (pintype "input"))
      (node (ref "E5") (pin "11") (pinfunction "QD_11") (pintype "output"))
      (node (ref "G910") (pin "1") (pinfunction "1_1") (pintype "passive"))
    )
    (net (code "11") (name "BTP3") (class "Default")
      (node (ref "E25") (pin "2") (pinfunction "I1_2") (pintype "input"))
      (node (ref "E34") (pin "14") (pinfunction "O_14") (pintype "output"))
      (node (ref "E41") (pin "13") (pinfunction "I1_13") (pintype "input"))
      (node (ref "E42") (pin "3") (pinfunction "I_3") (pintype "input"))
      (node (ref "E44") (pin "13") (pinfunction "I1_13") (pintype "input"))
    )
    (net (code "12") (name "B_PAUSE_L") (class "Default")
      (node (ref "E1") (pin "5") (pinfunction "I1_5") (pintype "input"))
      (node (ref "E1") (pin "6") (pinfunction "I0_6") (pintype "input"))
      (node (ref "E1") (pin "9") (pinfunction "I0_9") (pintype "input"))
      (node (ref "E23") (pin "10") (pinfunction "I1_10") (pintype "input"))
      (node (ref "E23") (pin "11") (pinfunction "I0_11") (pintype "input"))
      (node (ref "E23") (pin "6") (pinfunction "I0_6") (pintype "input"))
      (node (ref "E34") (pin "13") (pinfunction "O_13") (pintype "output"))
      (node (ref "E34") (pin "5") (pinfunction "I1_5") (pintype "input"))
    )
    (net (code "13") (name "C0_L") (class "Default")
      (node (ref "E33") (pin "1") (pinfunction "O_1") (pintype "open_collector"))
      (node (ref "U$2") (pin "CE1") (pinfunction "1_CE1") (pintype "bidirectional"))
    )
    (net (code "14") (name "C1_L") (class "Default")
      (node (ref "E33") (pin "13") (pinfunction "O_13") (pintype "open_collector"))
      (node (ref "E33") (pin "4") (pinfunction "O_4") (pintype "open_collector"))
      (node (ref "U$2") (pin "CH1") (pinfunction "1_CH1") (pintype "bidirectional"))
    )
    (net (code "15") (name "CKKCF") (class "Default")
      (node (ref "E47") (pin "3") (pinfunction "I1_3") (pintype "input"))
      (node (ref "E47") (pin "4") (pinfunction "O_4") (pintype "output"))
    )
    (net (code "16") (name "CKKIE") (class "Default")
      (node (ref "E38") (pin "11") (pinfunction "CLK_11") (pintype "input"))
      (node (ref "E47") (pin "10") (pinfunction "O_10") (pintype "output"))
    )
    (net (code "17") (name "CKTCF") (class "Default")
      (node (ref "E41") (pin "11") (pinfunction "O_11") (pintype "output"))
      (node (ref "E41") (pin "2") (pinfunction "I1_2") (pintype "input"))
    )
    (net (code "18") (name "CKTFL") (class "Default")
      (node (ref "E42") (pin "1") (pinfunction "I_1") (pintype "input"))
      (node (ref "E45") (pin "1") (pinfunction "O_1") (pintype "output"))
    )
    (net (code "19") (name "CK_PULSE") (class "Default")
      (node (ref "E11") (pin "5") (pinfunction "I0_5") (pintype "input"))
      (node (ref "E3") (pin "8") (pinfunction "~{Q}_8") (pintype "output"))
      (node (ref "E39") (pin "10") (pinfunction "I1_10") (pintype "input"))
      (node (ref "E48") (pin "3") (pinfunction "CLK_3") (pintype "input"))
      (node (ref "E8") (pin "3") (pinfunction "CLK_3") (pintype "input"))
    )
    (net (code "20") (name "DATA04_L") (class "Default")
      (node (ref "E2") (pin "13") (pinfunction "O_13") (pintype "open_collector"))
      (node (ref "E27") (pin "7") (pinfunction "I1_7") (pintype "input"))
      (node (ref "U$2") (pin "BR1") (pinfunction "1_BR1") (pintype "bidirectional"))
    )
    (net (code "21") (name "DATA05_L") (class "Default")
      (node (ref "E2") (pin "10") (pinfunction "O_10") (pintype "open_collector"))
      (node (ref "E27") (pin "4") (pinfunction "I0_4") (pintype "input"))
      (node (ref "U$2") (pin "BS1") (pinfunction "1_BS1") (pintype "bidirectional"))
    )
    (net (code "22") (name "DATA06_L") (class "Default")
      (node (ref "E2") (pin "4") (pinfunction "O_4") (pintype "open_collector"))
      (node (ref "E27") (pin "12") (pinfunction "I1_12") (pintype "input"))
      (node (ref "U$2") (pin "BU1") (pinfunction "1_BU1") (pintype "bidirectional"))
    )
    (net (code "23") (name "DATA07_L") (class "Default")
      (node (ref "E2") (pin "1") (pinfunction "O_1") (pintype "open_collector"))
      (node (ref "E27") (pin "9") (pinfunction "I0_9") (pintype "input"))
      (node (ref "U$2") (pin "BV1") (pinfunction "1_BV1") (pintype "bidirectional"))
    )
    (net (code "24") (name "DATA08_L") (class "Default")
      (node (ref "E15") (pin "13") (pinfunction "O_13") (pintype "open_collector"))
      (node (ref "E30") (pin "7") (pinfunction "I1_7") (pintype "input"))
      (node (ref "U$2") (pin "DR1") (pinfunction "1_DR1") (pintype "bidirectional"))
    )
    (net (code "25") (name "DATA09_L") (class "Default")
      (node (ref "E15") (pin "10") (pinfunction "O_10") (pintype "open_collector"))
      (node (ref "E30") (pin "4") (pinfunction "I0_4") (pintype "input"))
      (node (ref "U$2") (pin "DS1") (pinfunction "1_DS1") (pintype "bidirectional"))
    )
    (net (code "26") (name "DATA10_L") (class "Default")
      (node (ref "E15") (pin "4") (pinfunction "O_4") (pintype "open_collector"))
      (node (ref "E30") (pin "12") (pinfunction "I1_12") (pintype "input"))
      (node (ref "U$2") (pin "DU1") (pinfunction "1_DU1") (pintype "bidirectional"))
    )
    (net (code "27") (name "DATA11_L") (class "Default")
      (node (ref "E15") (pin "1") (pinfunction "O_1") (pintype "open_collector"))
      (node (ref "E30") (pin "9") (pinfunction "I0_9") (pintype "input"))
      (node (ref "E34") (pin "7") (pinfunction "I1_7") (pintype "input"))
      (node (ref "U$2") (pin "DV1") (pinfunction "1_DV1") (pintype "bidirectional"))
    )
    (net (code "28") (name "DOKCC") (class "Default")
      (node (ref "E33") (pin "11") (pinfunction "I0_11") (pintype "input"))
      (node (ref "E33") (pin "12") (pinfunction "I1_12") (pintype "input"))
      (node (ref "E33") (pin "2") (pinfunction "I0_2") (pintype "input"))
      (node (ref "E33") (pin "3") (pinfunction "I1_3") (pintype "input"))
      (node (ref "E44") (pin "12") (pinfunction "I0_12") (pintype "input"))
      (node (ref "E44") (pin "8") (pinfunction "O_8") (pintype "output"))
    )
    (net (code "29") (name "DOKRS") (class "Default")
      (node (ref "E15") (pin "11") (pinfunction "I0_11") (pintype "input"))
      (node (ref "E15") (pin "3") (pinfunction "I1_3") (pintype "input"))
      (node (ref "E15") (pin "5") (pinfunction "I0_5") (pintype "input"))
      (node (ref "E15") (pin "9") (pinfunction "I1_9") (pintype "input"))
      (node (ref "E2") (pin "11") (pinfunction "I0_11") (pintype "input"))
      (node (ref "E2") (pin "3") (pinfunction "I1_3") (pintype "input"))
      (node (ref "E2") (pin "5") (pinfunction "I0_5") (pintype "input"))
      (node (ref "E2") (pin "9") (pinfunction "I1_9") (pintype "input"))
      (node (ref "E33") (pin "5") (pinfunction "I0_5") (pintype "input"))
      (node (ref "E33") (pin "6") (pinfunction "I1_6") (pintype "input"))
      (node (ref "E44") (pin "6") (pinfunction "O_6") (pintype "output"))
    )
    (net (code "30") (name "DOTCF") (class "Default")
      (node (ref "E41") (pin "12") (pinfunction "I0_12") (pintype "input"))
      (node (ref "E41") (pin "8") (pinfunction "O_8") (pintype "output"))
    )
    (net (code "31") (name "DOTPC") (class "Default")
      (node (ref "E25") (pin "3") (pinfunction "I2_3") (pintype "input"))
      (node (ref "E29") (pin "12") (pinfunction "D_12") (pintype "input"))
      (node (ref "E35") (pin "1") (pinfunction "I0_1") (pintype "input"))
      (node (ref "E35") (pin "2") (pinfunction "I1_2") (pintype "input"))
      (node (ref "E41") (pin "6") (pinfunction "O_6") (pintype "output"))
    )
    (net (code "32") (name "EIA_IN") (class "Default")
      (node (ref "E17") (pin "1") (pinfunction "I_1") (pintype "input"))
      (node (ref "J1") (pin "J") (pinfunction "8_J") (pintype "bidirectional"))
    )
    (net (code "33") (name "EIA_OUT") (class "Default")
      (node (ref "E32") (pin "3") (pinfunction "O_3") (pintype "output"))
      (node (ref "J1") (pin "F") (pinfunction "6_F") (pintype "bidirectional"))
    )
    (net (code "34") (name "ENAB") (class "Default")
      (node (ref "E24") (pin "2") (pinfunction "I1_2") (pintype "input"))
      (node (ref "E25") (pin "13") (pinfunction "I3_13") (pintype "input"))
      (node (ref "E28") (pin "4") (pinfunction "D_4") (pintype "input"))
      (node (ref "E29") (pin "9") (pinfunction "Q_9") (pintype "output"))
    )
    (net (code "35") (name "FLGS") (class "Default")
      (node (ref "E37") (pin "11") (pinfunction "I0_11") (pintype "input"))
      (node (ref "E39") (pin "3") (pinfunction "I2_3") (pintype "input"))
      (node (ref "E44") (pin "3") (pinfunction "O_3") (pintype "output"))
    )
    (net (code "36") (name "GND") (class "Default")
      (node (ref "C1") (pin "2") (pinfunction "2_2") (pintype "passive"))
      (node (ref "C10") (pin "2") (pinfunction "2_2") (pintype "passive"))
      (node (ref "C11") (pin "2") (pinfunction "2_2") (pintype "passive"))
      (node (ref "C12") (pin "2") (pinfunction "2_2") (pintype "passive"))
      (node (ref "C13") (pin "2") (pinfunction "2_2") (pintype "passive"))
      (node (ref "C14") (pin "2") (pinfunction "2_2") (pintype "passive"))
      (node (ref "C15") (pin "2") (pinfunction "2_2") (pintype "passive"))
      (node (ref "C16") (pin "2") (pinfunction "2_2") (pintype "passive"))
      (node (ref "C17") (pin "2") (pinfunction "2_2") (pintype "passive"))
      (node (ref "C18") (pin "2") (pinfunction "2_2") (pintype "passive"))
      (node (ref "C19") (pin "2") (pinfunction "2_2") (pintype "passive"))
      (node (ref "C2") (pin "2") (pinfunction "2_2") (pintype "passive"))
      (node (ref "C20") (pin "2") (pinfunction "2_2") (pintype "passive"))
      (node (ref "C21") (pin "2") (pinfunction "2_2") (pintype "passive"))
      (node (ref "C22") (pin "2") (pinfunction "2_2") (pintype "passive"))
      (node (ref "C23") (pin "2") (pinfunction "2_2") (pintype "passive"))
      (node (ref "C24") (pin "2") (pinfunction "2_2") (pintype "passive"))
      (node (ref "C25") (pin "2") (pinfunction "2_2") (pintype "passive"))
      (node (ref "C26") (pin "2") (pinfunction "2_2") (pintype "passive"))
      (node (ref "C27") (pin "2") (pinfunction "2_2") (pintype "passive"))
      (node (ref "C28") (pin "2") (pinfunction "2_2") (pintype "passive"))
      (node (ref "C29") (pin "2") (pinfunction "2_2") (pintype "passive"))
      (node (ref "C3") (pin "2") (pinfunction "2_2") (pintype "passive"))
      (node (ref "C30") (pin "2") (pinfunction "2_2") (pintype "passive"))
      (node (ref "C31") (pin "2") (pinfunction "2_2") (pintype "passive"))
      (node (ref "C32") (pin "2") (pinfunction "2_2") (pintype "passive"))
      (node (ref "C33") (pin "2") (pinfunction "2_2") (pintype "passive"))
      (node (ref "C34") (pin "2") (pinfunction "2_2") (pintype "passive"))
      (node (ref "C35") (pin "2") (pinfunction "2_2") (pintype "passive"))
      (node (ref "C36") (pin "2") (pinfunction "2_2") (pintype "passive"))
      (node (ref "C37") (pin "2") (pinfunction "2_2") (pintype "passive"))
      (node (ref "C38") (pin "2") (pinfunction "2_2") (pintype "passive"))
      (node (ref "C39") (pin "2") (pinfunction "2_2") (pintype "passive"))
      (node (ref "C4") (pin "2") (pinfunction "2_2") (pintype "passive"))
      (node (ref "C40") (pin "2") (pinfunction "2_2") (pintype "passive"))
      (node (ref "C41") (pin "2") (pinfunction "2_2") (pintype "passive"))
      (node (ref "C42") (pin "2") (pinfunction "2_2") (pintype "passive"))
      (node (ref "C43") (pin "2") (pinfunction "2_2") (pintype "passive"))
      (node (ref "C44") (pin "2") (pinfunction "2_2") (pintype "passive"))
      (node (ref "C45") (pin "2") (pinfunction "2_2") (pintype "passive"))
      (node (ref "C46") (pin "2") (pinfunction "2_2") (pintype "passive"))
      (node (ref "C47") (pin "2") (pinfunction "2_2") (pintype "passive"))
      (node (ref "C48") (pin "2") (pinfunction "2_2") (pintype "passive"))
      (node (ref "C49") (pin "2") (pinfunction "2_2") (pintype "passive"))
      (node (ref "C5") (pin "2") (pinfunction "2_2") (pintype "passive"))
      (node (ref "C50") (pin "2") (pinfunction "2_2") (pintype "passive"))
      (node (ref "C51") (pin "-") (pinfunction "-_-") (pintype "passive"))
      (node (ref "C52") (pin "-") (pinfunction "-_-") (pintype "passive"))
      (node (ref "C53") (pin "-") (pinfunction "-_-") (pintype "passive"))
      (node (ref "C54") (pin "-") (pinfunction "-_-") (pintype "passive"))
      (node (ref "C55") (pin "+") (pinfunction "+_+") (pintype "passive"))
      (node (ref "C56") (pin "-") (pinfunction "-_-") (pintype "passive"))
      (node (ref "C57") (pin "2") (pinfunction "2_2") (pintype "passive"))
      (node (ref "C6") (pin "2") (pinfunction "2_2") (pintype "passive"))
      (node (ref "C60") (pin "2") (pinfunction "2_2") (pintype "passive"))
      (node (ref "C62") (pin "2") (pinfunction "2_2") (pintype "passive"))
      (node (ref "C66") (pin "-") (pinfunction "-_-") (pintype "passive"))
      (node (ref "C67") (pin "2") (pinfunction "2_2") (pintype "passive"))
      (node (ref "C7") (pin "2") (pinfunction "2_2") (pintype "passive"))
      (node (ref "C8") (pin "2") (pinfunction "2_2") (pintype "passive"))
      (node (ref "C9") (pin "2") (pinfunction "2_2") (pintype "passive"))
      (node (ref "D1") (pin "C") (pinfunction "C_C") (pintype "passive"))
      (node (ref "D2") (pin "C") (pinfunction "C_C") (pintype "passive"))
      (node (ref "D5") (pin "C") (pinfunction "C_C") (pintype "passive"))
      (node (ref "D8") (pin "A") (pinfunction "A_A") (pintype "passive"))
      (node (ref "DL1") (pin "2") (pinfunction "2_2") (pintype "passive"))
      (node (ref "E13") (pin "2") (pinfunction "R0(1)_2") (pintype "input"))
      (node (ref "E13") (pin "3") (pinfunction "R0(2)_3") (pintype "input"))
      (node (ref "E16") (pin "12") (pinfunction "D_12") (pintype "input"))
      (node (ref "E18") (pin "2") (pinfunction "R0(1)_2") (pintype "input"))
      (node (ref "E18") (pin "3") (pinfunction "R0(2)_3") (pintype "input"))
      (node (ref "E22") (pin "1") (pinfunction "B_1") (pintype "input"))
      (node (ref "E22") (pin "10") (pinfunction "C_10") (pintype "input"))
      (node (ref "E22") (pin "14") (pinfunction "CLR_14") (pintype "input"))
      (node (ref "E22") (pin "15") (pinfunction "A_15") (pintype "input"))
      (node (ref "E22") (pin "9") (pinfunction "D_9") (pintype "input"))
      (node (ref "E3") (pin "12") (pinfunction "D_12") (pintype "input"))
      (node (ref "E32") (pin "4") (pinfunction "I0_4") (pintype "input"))
      (node (ref "E32") (pin "5") (pinfunction "I1_5") (pintype "input"))
      (node (ref "E34") (pin "10") (pinfunction "I1_10") (pintype "input"))
      (node (ref "E34") (pin "11") (pinfunction "I0_11") (pintype "input"))
      (node (ref "E34") (pin "4") (pinfunction "I0_4") (pintype "input"))
      (node (ref "E36") (pin "10") (pinfunction "I1_10") (pintype "input"))
      (node (ref "E36") (pin "11") (pinfunction "I0_11") (pintype "input"))
      (node (ref "E5") (pin "2") (pinfunction "R0(1)_2") (pintype "input"))
      (node (ref "E5") (pin "3") (pinfunction "R0(2)_3") (pintype "input"))
      (node (ref "E7") (pin "12") (pinfunction "D_12") (pintype "input"))
      (node (ref "E7") (pin "2") (pinfunction "D_2") (pintype "input"))
      (node (ref "J1") (pin "A") (pinfunction "1_A") (pintype "bidirectional"))
      (node (ref "J1") (pin "B") (pinfunction "2_B") (pintype "bidirectional"))
      (node (ref "J1") (pin "C") (pinfunction "3_C") (pintype "bidirectional"))
      (node (ref "J1") (pin "UU") (pinfunction "39_UU") (pintype "bidirectional"))
      (node (ref "J1") (pin "VV") (pinfunction "40_VV") (pintype "bidirectional"))
      (node (ref "R2") (pin "1") (pinfunction "1_1") (pintype "passive"))
      (node (ref "R20") (pin "2") (pinfunction "2_2") (pintype "passive"))
      (node (ref "T1") (pin "4") (pinfunction "4_4") (pintype "passive"))
      (node (ref "T1") (pin "8") (pinfunction "8_8") (pintype "passive"))
      (node (ref "U$2") (pin "AC2") (pinfunction "1_AC2") (pintype "bidirectional"))
      (node (ref "U$2") (pin "AF1") (pinfunction "1_AF1") (pintype "bidirectional"))
      (node (ref "U$2") (pin "AF2") (pinfunction "1_AF2") (pintype "bidirectional"))
      (node (ref "U$2") (pin "AN1") (pinfunction "1_AN1") (pintype "bidirectional"))
      (node (ref "U$2") (pin "AN2") (pinfunction "1_AN2") (pintype "bidirectional"))
      (node (ref "U$2") (pin "AT1") (pinfunction "1_AT1") (pintype "bidirectional"))
      (node (ref "U$2") (pin "AT2") (pinfunction "1_AT2") (pintype "bidirectional"))
      (node (ref "U$2") (pin "BC1") (pinfunction "1_BC1") (pintype "bidirectional"))
      (node (ref "U$2") (pin "BC2") (pinfunction "1_BC2") (pintype "bidirectional"))
      (node (ref "U$2") (pin "BF1") (pinfunction "1_BF1") (pintype "bidirectional"))
      (node (ref "U$2") (pin "BF2") (pinfunction "1_BF2") (pintype "bidirectional"))
      (node (ref "U$2") (pin "BN1") (pinfunction "1_BN1") (pintype "bidirectional"))
      (node (ref "U$2") (pin "BN2") (pinfunction "1_BN2") (pintype "bidirectional"))
      (node (ref "U$2") (pin "BT1") (pinfunction "1_BT1") (pintype "bidirectional"))
      (node (ref "U$2") (pin "BT2") (pinfunction "1_BT2") (pintype "bidirectional"))
      (node (ref "U$2") (pin "CC1") (pinfunction "1_CC1") (pintype "bidirectional"))
      (node (ref "U$2") (pin "CC2") (pinfunction "1_CC2") (pintype "bidirectional"))
      (node (ref "U$2") (pin "CF1") (pinfunction "1_CF1") (pintype "bidirectional"))
      (node (ref "U$2") (pin "CF2") (pinfunction "1_CF2") (pintype "bidirectional"))
      (node (ref "U$2") (pin "CN1") (pinfunction "1_CN1") (pintype "bidirectional"))
      (node (ref "U$2") (pin "CN2") (pinfunction "1_CN2") (pintype "bidirectional"))
      (node (ref "U$2") (pin "CT1") (pinfunction "1_CT1") (pintype "bidirectional"))
      (node (ref "U$2") (pin "CT2") (pinfunction "1_CT2") (pintype "bidirectional"))
      (node (ref "U$2") (pin "DC1") (pinfunction "1_DC1") (pintype "bidirectional"))
      (node (ref "U$2") (pin "DC2") (pinfunction "1_DC2") (pintype "bidirectional"))
      (node (ref "U$2") (pin "DF1") (pinfunction "1_DF1") (pintype "bidirectional"))
      (node (ref "U$2") (pin "DF2") (pinfunction "1_DF2") (pintype "bidirectional"))
      (node (ref "U$2") (pin "DN1") (pinfunction "1_DN1") (pintype "bidirectional"))
      (node (ref "U$2") (pin "DN2") (pinfunction "1_DN2") (pintype "bidirectional"))
      (node (ref "U$2") (pin "DT1") (pinfunction "1_DT1") (pintype "bidirectional"))
      (node (ref "U$2") (pin "DT2") (pinfunction "1_DT2") (pintype "bidirectional"))
      (node (ref "Y1") (pin "2") (pinfunction "2_2") (pintype "passive"))
    )
    (net (code "37") (name "INITIALIZE") (class "Default")
      (node (ref "E36") (pin "9") (pinfunction "I0_9") (pintype "input"))
      (node (ref "U$2") (pin "CR1") (pinfunction "1_CR1") (pintype "bidirectional"))
    )
    (net (code "38") (name "INIT_L") (class "Default")
      (node (ref "E20") (pin "4") (pinfunction "PRE_4") (pintype "input"))
      (node (ref "E28") (pin "1") (pinfunction "R_1") (pintype "input"))
      (node (ref "E31") (pin "1") (pinfunction "R_1") (pintype "input"))
      (node (ref "E35") (pin "11") (pinfunction "O_11") (pintype "output"))
      (node (ref "E35") (pin "5") (pinfunction "I1_5") (pintype "input"))
      (node (ref "E38") (pin "13") (pinfunction "CLR_13") (pintype "input"))
      (node (ref "E41") (pin "1") (pinfunction "I0_1") (pintype "input"))
    )
    (net (code "39") (name "INTERNAL_IO_L") (class "Default")
      (node (ref "E37") (pin "1") (pinfunction "O_1") (pintype "open_collector"))
      (node (ref "E37") (pin "4") (pinfunction "O_4") (pintype "open_collector"))
      (node (ref "U$2") (pin "CL1") (pinfunction "1_CL1") (pintype "bidirectional"))
    )
    (net (code "40") (name "INT_ENAB") (class "Default")
      (node (ref "E37") (pin "12") (pinfunction "I1_12") (pintype "input"))
      (node (ref "E38") (pin "8") (pinfunction "~{Q}_8") (pintype "output"))
      (node (ref "U$2") (pin "CB1") (pinfunction "1_CB1") (pintype "bidirectional"))
    )
    (net (code "41") (name "INT_RQST_L") (class "Default")
      (node (ref "E37") (pin "13") (pinfunction "O_13") (pintype "open_collector"))
      (node (ref "U$2") (pin "CP1") (pinfunction "1_CP1") (pintype "bidirectional"))
    )
    (net (code "42") (name "IO_PAUSE_L") (class "Default")
      (node (ref "E34") (pin "12") (pinfunction "I1_12") (pintype "input"))
      (node (ref "U$2") (pin "CD1") (pinfunction "1_CD1") (pintype "bidirectional"))
    )
    (net (code "43") (name "KSKP") (class "Default")
      (node (ref "E45") (pin "5") (pinfunction "I0_5") (pintype "input"))
      (node (ref "E47") (pin "13") (pinfunction "O_13") (pintype "output"))
    )
    (net (code "44") (name "LAST_UNIT") (class "Default")
      (node (ref "E39") (pin "13") (pinfunction "I3_13") (pintype "input"))
      (node (ref "E8") (pin "5") (pinfunction "Q_5") (pintype "output"))
    )
    (net (code "45") (name "LINE") (class "Default")
      (node (ref "E29") (pin "5") (pinfunction "Q_5") (pintype "output"))
      (node (ref "E32") (pin "2") (pinfunction "I_2") (pintype "input"))
      (node (ref "U$2") (pin "DA1") (pinfunction "1_DA1") (pintype "bidirectional"))
    )
    (net (code "46") (name "MD03") (class "Default")
      (node (ref "B") (pin "4") (pinfunction "4_4") (pintype "passive"))
      (node (ref "E1") (pin "10") (pinfunction "I1_10") (pintype "input"))
      (node (ref "U$2") (pin "AP1") (pinfunction "1_AP1") (pintype "bidirectional"))
    )
    (net (code "47") (name "MD04") (class "Default")
      (node (ref "A") (pin "4") (pinfunction "4_4") (pintype "passive"))
      (node (ref "E1") (pin "7") (pinfunction "I1_7") (pintype "input"))
      (node (ref "U$2") (pin "BK1") (pinfunction "1_BK1") (pintype "bidirectional"))
    )
    (net (code "48") (name "MD05") (class "Default")
      (node (ref "E23") (pin "9") (pinfunction "I0_9") (pintype "input"))
      (node (ref "F") (pin "3") (pinfunction "3_3") (pintype "passive"))
      (node (ref "U$2") (pin "BL1") (pinfunction "1_BL1") (pintype "bidirectional"))
    )
    (net (code "49") (name "MD06") (class "Default")
      (node (ref "E") (pin "3") (pinfunction "3_3") (pintype "passive"))
      (node (ref "E23") (pin "12") (pinfunction "I1_12") (pintype "input"))
      (node (ref "JE13") (pin "1") (pinfunction "1_1") (pintype "passive"))
      (node (ref "U$2") (pin "BM1") (pinfunction "1_BM1") (pintype "bidirectional"))
    )
    (net (code "50") (name "MD07") (class "Default")
      (node (ref "D") (pin "4") (pinfunction "4_4") (pintype "passive"))
      (node (ref "E23") (pin "7") (pinfunction "I1_7") (pintype "input"))
      (node (ref "JD24") (pin "1") (pinfunction "1_1") (pintype "passive"))
      (node (ref "U$2") (pin "BP1") (pinfunction "1_BP1") (pintype "bidirectional"))
    )
    (net (code "51") (name "MD08") (class "Default")
      (node (ref "C") (pin "4") (pinfunction "4_4") (pintype "passive"))
      (node (ref "E1") (pin "4") (pinfunction "I0_4") (pintype "input"))
      (node (ref "JC24") (pin "1") (pinfunction "1_1") (pintype "passive"))
      (node (ref "U$2") (pin "DK1") (pinfunction "1_DK1") (pintype "bidirectional"))
    )
    (net (code "52") (name "MD09") (class "Default")
      (node (ref "E46") (pin "7") (pinfunction "I1_7") (pintype "input"))
      (node (ref "U$2") (pin "DL1") (pinfunction "1_DL1") (pintype "bidirectional"))
    )
    (net (code "53") (name "MD10") (class "Default")
      (node (ref "E46") (pin "4") (pinfunction "I0_4") (pintype "input"))
      (node (ref "U$2") (pin "DM1") (pinfunction "1_DM1") (pintype "bidirectional"))
    )
    (net (code "54") (name "MD11") (class "Default")
      (node (ref "E46") (pin "9") (pinfunction "I0_9") (pintype "input"))
      (node (ref "U$2") (pin "DP1") (pinfunction "1_DP1") (pintype "bidirectional"))
    )
    (net (code "55") (name "Net-(C58-Pad2)") (class "Default")
      (node (ref "C58") (pin "2") (pinfunction "2_2") (pintype "passive"))
      (node (ref "C67") (pin "1") (pinfunction "1_1") (pintype "passive"))
      (node (ref "Y1") (pin "1") (pinfunction "1_1") (pintype "passive"))
    )
    (net (code "56") (name "Net-(C61-Pad2)") (class "Default")
      (node (ref "C61") (pin "2") (pinfunction "2_2") (pintype "passive"))
      (node (ref "R4") (pin "2") (pinfunction "2_2") (pintype "passive"))
      (node (ref "T1") (pin "1") (pinfunction "1_1") (pintype "passive"))
      (node (ref "T1") (pin "5") (pinfunction "5_5") (pintype "passive"))
    )
    (net (code "57") (name "Net-(C66-Pad+)") (class "Default")
      (node (ref "C66") (pin "+") (pinfunction "+_+") (pintype "passive"))
      (node (ref "D7") (pin "A") (pinfunction "A_A") (pintype "passive"))
      (node (ref "D8") (pin "C") (pinfunction "C_C") (pintype "passive"))
      (node (ref "R18") (pin "1") (pinfunction "1_1") (pintype "passive"))
      (node (ref "R22") (pin "2") (pinfunction "2_2") (pintype "passive"))
    )
    (net (code "58") (name "Net-(D1-PadA)") (class "Default")
      (node (ref "D1") (pin "A") (pinfunction "A_A") (pintype "passive"))
      (node (ref "R5") (pin "1") (pinfunction "1_1") (pintype "passive"))
      (node (ref "R7") (pin "1") (pinfunction "1_1") (pintype "passive"))
      (node (ref "T1") (pin "9") (pinfunction "9_9") (pintype "passive"))
    )
    (net (code "59") (name "Net-(D2-PadA)") (class "Default")
      (node (ref "D2") (pin "A") (pinfunction "A_A") (pintype "passive"))
      (node (ref "D3") (pin "C") (pinfunction "C_C") (pintype "passive"))
    )
    (net (code "60") (name "Net-(D3-PadA)") (class "Default")
      (node (ref "D3") (pin "A") (pinfunction "A_A") (pintype "passive"))
      (node (ref "D4") (pin "C") (pinfunction "C_C") (pintype "passive"))
    )
    (net (code "61") (name "Net-(D10-PadC)") (class "Default")
      (node (ref "D10") (pin "C") (pinfunction "C_C") (pintype "passive"))
      (node (ref "D11") (pin "A") (pinfunction "A_A") (pintype "passive"))
    )
    (net (code "62") (name "Net-(D11-PadC)") (class "Default")
      (node (ref "D11") (pin "C") (pinfunction "C_C") (pintype "passive"))
      (node (ref "D12") (pin "A") (pinfunction "A_A") (pintype "passive"))
    )
    (net (code "63") (name "Net-(D13-PadA)") (class "Default")
      (node (ref "D13") (pin "A") (pinfunction "A_A") (pintype "passive"))
      (node (ref "D14") (pin "C") (pinfunction "C_C") (pintype "passive"))
    )
    (net (code "64") (name "Net-(D14-PadA)") (class "Default")
      (node (ref "D14") (pin "A") (pinfunction "A_A") (pintype "passive"))
      (node (ref "D15") (pin "C") (pinfunction "C_C") (pintype "passive"))
    )
    (net (code "65") (name "Net-(E1A-O)") (class "Default")
      (node (ref "C") (pin "1") (pinfunction "1_1") (pintype "passive"))
      (node (ref "E1") (pin "3") (pinfunction "O_3") (pintype "output"))
      (node (ref "JC13") (pin "2") (pinfunction "2_2") (pintype "passive"))
    )
    (net (code "66") (name "Net-(E1B-O)") (class "Default")
      (node (ref "A") (pin "1") (pinfunction "1_1") (pintype "passive"))
      (node (ref "E1") (pin "2") (pinfunction "O_2") (pintype "output"))
      (node (ref "JA12") (pin "1") (pinfunction "1_1") (pintype "passive"))
      (node (ref "JA13") (pin "2") (pinfunction "2_2") (pintype "passive"))
    )
    (net (code "67") (name "Net-(E1C-O)") (class "Default")
      (node (ref "B") (pin "1") (pinfunction "1_1") (pintype "passive"))
      (node (ref "E1") (pin "14") (pinfunction "O_14") (pintype "output"))
      (node (ref "JB12") (pin "1") (pinfunction "1_1") (pintype "passive"))
      (node (ref "JB13") (pin "2") (pinfunction "2_2") (pintype "passive"))
    )
    (net (code "68") (name "Net-(E1D-O)") (class "Default")
      (node (ref "E1") (pin "13") (pinfunction "O_13") (pintype "output"))
      (node (ref "E48") (pin "11") (pinfunction "CLK_11") (pintype "input"))
    )
    (net (code "69") (name "Net-(E2B-I1)") (class "Default")
      (node (ref "E2") (pin "6") (pinfunction "I1_6") (pintype "input"))
      (node (ref "E6") (pin "9") (pinfunction "Q2_9") (pintype "output"))
    )
    (net (code "70") (name "Net-(E2C-I0)") (class "Default")
      (node (ref "E2") (pin "8") (pinfunction "I0_8") (pintype "input"))
      (node (ref "E6") (pin "7") (pinfunction "Q1_7") (pintype "output"))
    )
    (net (code "71") (name "Net-(E5A-CKB)") (class "Default")
      (node (ref "E5") (pin "1") (pinfunction "CKB_1") (pintype "input"))
      (node (ref "E5") (pin "12") (pinfunction "QA_12") (pintype "output"))
    )
    (net (code "72") (name "Net-(E8B-D)") (class "Default")
      (node (ref "E8") (pin "12") (pinfunction "D_12") (pintype "input"))
      (node (ref "E8") (pin "8") (pinfunction "~{Q}_8") (pintype "output"))
    )
    (net (code "73") (name "Net-(E9A-I0)") (class "Default")
      (node (ref "E9") (pin "4") (pinfunction "I0_4") (pintype "input"))
      (node (ref "F") (pin "1") (pinfunction "1_1") (pintype "passive"))
      (node (ref "JF12") (pin "2") (pinfunction "2_2") (pintype "passive"))
    )
    (net (code "74") (name "Net-(E9A-I2)") (class "Default")
      (node (ref "E") (pin "4") (pinfunction "4_4") (pintype "passive"))
      (node (ref "E9") (pin "6") (pinfunction "I2_6") (pintype "input"))
      (node (ref "JE24") (pin "1") (pinfunction "1_1") (pintype "passive"))
    )
    (net (code "75") (name "Net-(E9A-I3)") (class "Default")
      (node (ref "A") (pin "3") (pinfunction "3_3") (pintype "passive"))
      (node (ref "E9") (pin "9") (pinfunction "I3_9") (pintype "input"))
      (node (ref "JA13") (pin "1") (pinfunction "1_1") (pintype "passive"))
    )
    (net (code "76") (name "Net-(E9A-I4)") (class "Default")
      (node (ref "C") (pin "2") (pinfunction "2_2") (pintype "passive"))
      (node (ref "E9") (pin "10") (pinfunction "I4_10") (pintype "input"))
      (node (ref "JC24") (pin "2") (pinfunction "2_2") (pintype "passive"))
    )
    (net (code "77") (name "Net-(E9A-I5)") (class "Default")
      (node (ref "B") (pin "2") (pinfunction "2_2") (pintype "passive"))
      (node (ref "E9") (pin "11") (pinfunction "I5_11") (pintype "input"))
      (node (ref "JB12") (pin "2") (pinfunction "2_2") (pintype "passive"))
    )
    (net (code "78") (name "Net-(E9A-I6)") (class "Default")
      (node (ref "D") (pin "2") (pinfunction "2_2") (pintype "passive"))
      (node (ref "E9") (pin "12") (pinfunction "I6_12") (pintype "input"))
      (node (ref "JD24") (pin "2") (pinfunction "2_2") (pintype "passive"))
    )
    (net (code "79") (name "Net-(E10A-C)") (class "Default")
      (node (ref "E10") (pin "6") (pinfunction "C_6") (pintype "input"))
      (node (ref "E11") (pin "4") (pinfunction "O_4") (pintype "output"))
      (node (ref "E6") (pin "6") (pinfunction "C_6") (pintype "input"))
    )
    (net (code "80") (name "Net-(E10A-D)") (class "Default")
      (node (ref "E10") (pin "4") (pinfunction "D_4") (pintype "input"))
      (node (ref "E2") (pin "2") (pinfunction "I0_2") (pintype "input"))
      (node (ref "E6") (pin "11") (pinfunction "Q3_11") (pintype "output"))
    )
    (net (code "81") (name "Net-(E10A-Q0)") (class "Default")
      (node (ref "E10") (pin "5") (pinfunction "Q0_5") (pintype "output"))
      (node (ref "E15") (pin "12") (pinfunction "I1_12") (pintype "input"))
    )
    (net (code "82") (name "Net-(E10A-Q1)") (class "Default")
      (node (ref "E10") (pin "7") (pinfunction "Q1_7") (pintype "output"))
      (node (ref "E15") (pin "8") (pinfunction "I0_8") (pintype "input"))
    )
    (net (code "83") (name "Net-(E10A-Q2)") (class "Default")
      (node (ref "E10") (pin "9") (pinfunction "Q2_9") (pintype "output"))
      (node (ref "E15") (pin "6") (pinfunction "I1_6") (pintype "input"))
    )
    (net (code "84") (name "Net-(E10A-Q3)") (class "Default")
      (node (ref "E10") (pin "11") (pinfunction "Q3_11") (pintype "output"))
      (node (ref "E15") (pin "2") (pinfunction "I0_2") (pintype "input"))
    )
    (net (code "85") (name "Net-(E11A-O)") (class "Default")
      (node (ref "E11") (pin "1") (pinfunction "O_1") (pintype "output"))
      (node (ref "E39") (pin "9") (pinfunction "I2_9") (pintype "input"))
    )
    (net (code "86") (name "Net-(E11B-I1)") (class "Default")
      (node (ref "E11") (pin "10") (pinfunction "O_10") (pintype "output"))
      (node (ref "E11") (pin "6") (pinfunction "I1_6") (pintype "input"))
    )
    (net (code "87") (name "Net-(E11D-O)") (class "Default")
      (node (ref "E11") (pin "13") (pinfunction "O_13") (pintype "output"))
      (node (ref "E3") (pin "11") (pinfunction "CLK_11") (pintype "input"))
    )
    (net (code "88") (name "Net-(E12B-O)") (class "Default")
      (node (ref "E12") (pin "6") (pinfunction "O_6") (pintype "output"))
      (node (ref "E8") (pin "1") (pinfunction "CLR_1") (pintype "input"))
    )
    (net (code "89") (name "Net-(E12C-O)") (class "Default")
      (node (ref "E12") (pin "8") (pinfunction "O_8") (pintype "output"))
      (node (ref "E3") (pin "2") (pinfunction "D_2") (pintype "input"))
    )
    (net (code "90") (name "Net-(E14A-I0)") (class "Default")
      (node (ref "E") (pin "1") (pinfunction "1_1") (pintype "passive"))
      (node (ref "E14") (pin "4") (pinfunction "I0_4") (pintype "input"))
      (node (ref "JE13") (pin "2") (pinfunction "2_2") (pintype "passive"))
    )
    (net (code "91") (name "Net-(E14A-I1)") (class "Default")
      (node (ref "E14") (pin "5") (pinfunction "I1_5") (pintype "input"))
      (node (ref "F") (pin "4") (pinfunction "4_4") (pintype "passive"))
      (node (ref "JF24") (pin "1") (pinfunction "1_1") (pintype "passive"))
    )
    (net (code "92") (name "Net-(E14A-I2)") (class "Default")
      (node (ref "D") (pin "3") (pinfunction "3_3") (pintype "passive"))
      (node (ref "E14") (pin "6") (pinfunction "I2_6") (pintype "input"))
      (node (ref "JD13") (pin "1") (pinfunction "1_1") (pintype "passive"))
    )
    (net (code "93") (name "Net-(E14A-I3)") (class "Default")
      (node (ref "B") (pin "3") (pinfunction "3_3") (pintype "passive"))
      (node (ref "E14") (pin "9") (pinfunction "I3_9") (pintype "input"))
      (node (ref "JB13") (pin "1") (pinfunction "1_1") (pintype "passive"))
    )
    (net (code "94") (name "Net-(E14A-I4)") (class "Default")
      (node (ref "C") (pin "3") (pinfunction "3_3") (pintype "passive"))
      (node (ref "E14") (pin "10") (pinfunction "I4_10") (pintype "input"))
      (node (ref "JC13") (pin "1") (pinfunction "1_1") (pintype "passive"))
    )
    (net (code "95") (name "Net-(E14A-I5)") (class "Default")
      (node (ref "E14") (pin "11") (pinfunction "I5_11") (pintype "input"))
      (node (ref "E34") (pin "3") (pinfunction "O_3") (pintype "output"))
      (node (ref "E34") (pin "6") (pinfunction "I0_6") (pintype "input"))
      (node (ref "E9") (pin "5") (pinfunction "I1_5") (pintype "input"))
    )
    (net (code "96") (name "Net-(E14A-I6)") (class "Default")
      (node (ref "A") (pin "2") (pinfunction "2_2") (pintype "passive"))
      (node (ref "E14") (pin "12") (pinfunction "I6_12") (pintype "input"))
      (node (ref "JA12") (pin "2") (pinfunction "2_2") (pintype "passive"))
    )
    (net (code "97") (name "Net-(E14A-O)") (class "Default")
      (node (ref "E14") (pin "3") (pinfunction "O_3") (pintype "output"))
      (node (ref "E23") (pin "5") (pinfunction "I1_5") (pintype "input"))
      (node (ref "E33") (pin "8") (pinfunction "I0_8") (pintype "input"))
      (node (ref "E33") (pin "9") (pinfunction "I1_9") (pintype "input"))
      (node (ref "E37") (pin "2") (pinfunction "I0_2") (pintype "input"))
      (node (ref "E37") (pin "3") (pinfunction "I1_3") (pintype "input"))
    )
    (net (code "98") (name "Net-(E16A-D)") (class "Default")
      (node (ref "E16") (pin "2") (pinfunction "D_2") (pintype "input"))
      (node (ref "E35") (pin "8") (pinfunction "O_8") (pintype "output"))
    )
    (net (code "99") (name "Net-(E17A-O)") (class "Default")
      (node (ref "E17") (pin "3") (pinfunction "O_3") (pintype "output"))
      (node (ref "E21") (pin "13") (pinfunction "I_13") (pintype "input"))
    )
    (net (code "100") (name "Net-(E17A-RC)") (class "Default")
      (node (ref "E17") (pin "2") (pinfunction "RC_2") (pintype "input"))
      (node (ref "R23") (pin "1") (pinfunction "1_1") (pintype "passive"))
    )
    (net (code "101") (name "Net-(E18A-CKA)") (class "Default")
      (node (ref "E18") (pin "14") (pinfunction "CKA_14") (pintype "input"))
      (node (ref "G12") (pin "2") (pinfunction "2_2") (pintype "passive"))
      (node (ref "G34") (pin "2") (pinfunction "2_2") (pintype "passive"))
      (node (ref "G56") (pin "2") (pinfunction "2_2") (pintype "passive"))
      (node (ref "G78") (pin "2") (pinfunction "2_2") (pintype "passive"))
      (node (ref "G910") (pin "2") (pinfunction "2_2") (pintype "passive"))
      (node (ref "U$2") (pin "AA1") (pinfunction "1_AA1") (pintype "bidirectional"))
    )
    (net (code "102") (name "Net-(E18A-QD)") (class "Default")
      (node (ref "E18") (pin "11") (pinfunction "QD_11") (pintype "output"))
      (node (ref "H12") (pin "1") (pinfunction "1_1") (pintype "passive"))
      (node (ref "H123") (pin "1") (pinfunction "1_1") (pintype "passive"))
    )
    (net (code "103") (name "Net-(E19A-I1)") (class "Default")
      (node (ref "E19") (pin "2") (pinfunction "I1_2") (pintype "input"))
      (node (ref "E21") (pin "10") (pinfunction "O_10") (pintype "output"))
    )
    (net (code "104") (name "Net-(E19B-I0)") (class "Default")
      (node (ref "E19") (pin "11") (pinfunction "I2_11") (pintype "input"))
      (node (ref "E19") (pin "3") (pinfunction "I0_3") (pintype "input"))
      (node (ref "E24") (pin "8") (pinfunction "O_8") (pintype "output"))
    )
    (net (code "105") (name "Net-(E19B-I2)") (class "Default")
      (node (ref "E19") (pin "10") (pinfunction "I1_10") (pintype "input"))
      (node (ref "E19") (pin "5") (pinfunction "I2_5") (pintype "input"))
      (node (ref "E19") (pin "9") (pinfunction "I0_9") (pintype "input"))
      (node (ref "E24") (pin "6") (pinfunction "O_6") (pintype "output"))
    )
    (net (code "106") (name "Net-(E20A-D)") (class "Default")
      (node (ref "E20") (pin "2") (pinfunction "D_2") (pintype "input"))
      (node (ref "E25") (pin "8") (pinfunction "O_8") (pintype "output"))
    )
    (net (code "107") (name "Net-(E21A-I)") (class "Default")
      (node (ref "E21") (pin "1") (pinfunction "I_1") (pintype "input"))
      (node (ref "E39") (pin "8") (pinfunction "O_8") (pintype "output"))
    )
    (net (code "108") (name "Net-(E21A-O)") (class "Default")
      (node (ref "E21") (pin "2") (pinfunction "O_2") (pintype "output"))
      (node (ref "E7") (pin "3") (pinfunction "CLK_3") (pintype "input"))
    )
    (net (code "109") (name "Net-(E21B-O)") (class "Default")
      (node (ref "E21") (pin "4") (pinfunction "O_4") (pintype "output"))
      (node (ref "E29") (pin "11") (pinfunction "CLK_11") (pintype "input"))
    )
    (net (code "110") (name "Net-(E21C-O)") (class "Default")
      (node (ref "E21") (pin "6") (pinfunction "O_6") (pintype "output"))
      (node (ref "E26") (pin "6") (pinfunction "C_6") (pintype "input"))
    )
    (net (code "111") (name "Net-(E21D-O)") (class "Default")
      (node (ref "E21") (pin "8") (pinfunction "O_8") (pintype "output"))
      (node (ref "E6") (pin "4") (pinfunction "D_4") (pintype "input"))
    )
    (net (code "112") (name "Net-(E22A-QD)") (class "Default")
      (node (ref "E22") (pin "7") (pinfunction "QD_7") (pintype "output"))
      (node (ref "E5") (pin "14") (pinfunction "CKA_14") (pintype "input"))
    )
    (net (code "113") (name "Net-(E22A-UP)") (class "Default")
      (node (ref "E22") (pin "5") (pinfunction "UP_5") (pintype "input"))
      (node (ref "R6") (pin "2") (pinfunction "2_2") (pintype "passive"))
    )
    (net (code "114") (name "Net-(E23A-I0)") (class "Default")
      (node (ref "E23") (pin "4") (pinfunction "I0_4") (pintype "input"))
      (node (ref "E37") (pin "5") (pinfunction "I0_5") (pintype "input"))
      (node (ref "E37") (pin "6") (pinfunction "I1_6") (pintype "input"))
      (node (ref "E42") (pin "13") (pinfunction "I_13") (pintype "input"))
      (node (ref "E9") (pin "3") (pinfunction "O_3") (pintype "output"))
    )
    (net (code "115") (name "Net-(E23B-O)") (class "Default")
      (node (ref "D") (pin "1") (pinfunction "1_1") (pintype "passive"))
      (node (ref "E23") (pin "2") (pinfunction "O_2") (pintype "output"))
      (node (ref "JD13") (pin "2") (pinfunction "2_2") (pintype "passive"))
    )
    (net (code "116") (name "Net-(E23C-O)") (class "Default")
      (node (ref "E23") (pin "14") (pinfunction "O_14") (pintype "output"))
      (node (ref "F") (pin "2") (pinfunction "2_2") (pintype "passive"))
      (node (ref "JF12") (pin "1") (pinfunction "1_1") (pintype "passive"))
      (node (ref "JF24") (pin "2") (pinfunction "2_2") (pintype "passive"))
    )
    (net (code "117") (name "Net-(E23D-O)") (class "Default")
      (node (ref "E") (pin "2") (pinfunction "2_2") (pintype "passive"))
      (node (ref "E23") (pin "13") (pinfunction "O_13") (pintype "output"))
      (node (ref "JE24") (pin "2") (pinfunction "2_2") (pintype "passive"))
    )
    (net (code "118") (name "Net-(E24A-I0)") (class "Default")
      (node (ref "E24") (pin "1") (pinfunction "I0_1") (pintype "input"))
      (node (ref "E28") (pin "9") (pinfunction "Q2_9") (pintype "output"))
    )
    (net (code "119") (name "Net-(E24A-I2)") (class "Default")
      (node (ref "E24") (pin "4") (pinfunction "I2_4") (pintype "input"))
      (node (ref "E28") (pin "5") (pinfunction "Q0_5") (pintype "output"))
    )
    (net (code "120") (name "Net-(E24A-I3)") (class "Default")
      (node (ref "E24") (pin "5") (pinfunction "I3_5") (pintype "input"))
      (node (ref "E28") (pin "7") (pinfunction "Q1_7") (pintype "output"))
    )
    (net (code "121") (name "Net-(E24B-I0)") (class "Default")
      (node (ref "E24") (pin "9") (pinfunction "I0_9") (pintype "input"))
      (node (ref "E31") (pin "5") (pinfunction "Q0_5") (pintype "output"))
    )
    (net (code "122") (name "Net-(E24B-I1)") (class "Default")
      (node (ref "E24") (pin "10") (pinfunction "I1_10") (pintype "input"))
      (node (ref "E31") (pin "7") (pinfunction "Q1_7") (pintype "output"))
    )
    (net (code "123") (name "Net-(E24B-I2)") (class "Default")
      (node (ref "E24") (pin "12") (pinfunction "I2_12") (pintype "input"))
      (node (ref "E31") (pin "9") (pinfunction "Q2_9") (pintype "output"))
    )
    (net (code "124") (name "Net-(E24B-I3)") (class "Default")
      (node (ref "E24") (pin "13") (pinfunction "I3_13") (pintype "input"))
      (node (ref "E28") (pin "11") (pinfunction "Q3_11") (pintype "output"))
      (node (ref "E31") (pin "4") (pinfunction "D_4") (pintype "input"))
    )
    (net (code "125") (name "Net-(E25B-I4)") (class "Default")
      (node (ref "DL1") (pin "3") (pinfunction "3_3") (pintype "passive"))
      (node (ref "E25") (pin "5") (pinfunction "I4_5") (pintype "input"))
      (node (ref "R20") (pin "1") (pinfunction "1_1") (pintype "passive"))
    )
    (net (code "126") (name "Net-(E26A-Q0)") (class "Default")
      (node (ref "E26") (pin "5") (pinfunction "Q0_5") (pintype "output"))
      (node (ref "J23") (pin "3") (pinfunction "3_3") (pintype "passive"))
    )
    (net (code "127") (name "Net-(E26A-Q2)") (class "Default")
      (node (ref "E26") (pin "9") (pinfunction "Q2_9") (pintype "output"))
      (node (ref "J23") (pin "1") (pinfunction "1_1") (pintype "passive"))
      (node (ref "JJ23") (pin "1") (pinfunction "1_1") (pintype "passive"))
    )
    (net (code "128") (name "Net-(E27A-O)") (class "Default")
      (node (ref "E27") (pin "3") (pinfunction "O_3") (pintype "output"))
      (node (ref "E28") (pin "2") (pinfunction "I1_2") (pintype "input"))
    )
    (net (code "129") (name "Net-(E27B-O)") (class "Default")
      (node (ref "E27") (pin "2") (pinfunction "O_2") (pintype "output"))
      (node (ref "E28") (pin "3") (pinfunction "I0_3") (pintype "input"))
    )
    (net (code "130") (name "Net-(E27C-O)") (class "Default")
      (node (ref "E27") (pin "14") (pinfunction "O_14") (pintype "output"))
      (node (ref "E28") (pin "14") (pinfunction "I3_14") (pintype "input"))
    )
    (net (code "131") (name "Net-(E27D-O)") (class "Default")
      (node (ref "E27") (pin "13") (pinfunction "O_13") (pintype "output"))
      (node (ref "E28") (pin "15") (pinfunction "I2_15") (pintype "input"))
    )
    (net (code "132") (name "Net-(E30A-O)") (class "Default")
      (node (ref "E30") (pin "3") (pinfunction "O_3") (pintype "output"))
      (node (ref "E31") (pin "2") (pinfunction "I1_2") (pintype "input"))
    )
    (net (code "133") (name "Net-(E30B-O)") (class "Default")
      (node (ref "E30") (pin "2") (pinfunction "O_2") (pintype "output"))
      (node (ref "E31") (pin "3") (pinfunction "I0_3") (pintype "input"))
    )
    (net (code "134") (name "Net-(E30C-O)") (class "Default")
      (node (ref "E30") (pin "14") (pinfunction "O_14") (pintype "output"))
      (node (ref "E31") (pin "14") (pinfunction "I3_14") (pintype "input"))
    )
    (net (code "135") (name "Net-(E30D-O)") (class "Default")
      (node (ref "E30") (pin "13") (pinfunction "O_13") (pintype "output"))
      (node (ref "E31") (pin "15") (pinfunction "I2_15") (pintype "input"))
    )
    (net (code "136") (name "Net-(E34B-O)") (class "Default")
      (node (ref "E34") (pin "2") (pinfunction "O_2") (pintype "output"))
      (node (ref "E38") (pin "12") (pinfunction "D_12") (pintype "input"))
    )
    (net (code "137") (name "Net-(E35B-O)") (class "Default")
      (node (ref "E35") (pin "6") (pinfunction "O_6") (pintype "output"))
      (node (ref "E47") (pin "2") (pinfunction "I0_2") (pintype "input"))
    )
    (net (code "138") (name "Net-(E35D-I0)") (class "Default")
      (node (ref "E35") (pin "12") (pinfunction "I0_12") (pintype "input"))
      (node (ref "E35") (pin "13") (pinfunction "I1_13") (pintype "input"))
      (node (ref "E36") (pin "14") (pinfunction "O_14") (pintype "output"))
      (node (ref "E46") (pin "11") (pinfunction "I0_11") (pintype "input"))
      (node (ref "E46") (pin "12") (pinfunction "I1_12") (pintype "input"))
    )
    (net (code "139") (name "Net-(E36B-I0)") (class "Default")
      (node (ref "C65") (pin "1") (pinfunction "1_1") (pintype "passive"))
      (node (ref "E36") (pin "6") (pinfunction "I0_6") (pintype "input"))
      (node (ref "E36") (pin "7") (pinfunction "I1_7") (pintype "input"))
      (node (ref "R18") (pin "2") (pinfunction "2_2") (pintype "passive"))
      (node (ref "R19") (pin "1") (pinfunction "1_1") (pintype "passive"))
    )
    (net (code "140") (name "Net-(E36D-O)") (class "Default")
      (node (ref "E36") (pin "13") (pinfunction "O_13") (pintype "output"))
      (node (ref "E7") (pin "1") (pinfunction "CLR_1") (pintype "input"))
    )
    (net (code "141") (name "Net-(E37C-I0)") (class "Default")
      (node (ref "E37") (pin "8") (pinfunction "I0_8") (pintype "input"))
      (node (ref "E37") (pin "9") (pinfunction "I1_9") (pintype "input"))
      (node (ref "E42") (pin "8") (pinfunction "O_8") (pintype "output"))
    )
    (net (code "142") (name "Net-(E38A-PRE)") (class "Default")
      (node (ref "E38") (pin "4") (pinfunction "PRE_4") (pintype "input"))
      (node (ref "E42") (pin "6") (pinfunction "O_6") (pintype "output"))
    )
    (net (code "143") (name "Net-(E39B-I1)") (class "Default")
      (node (ref "E39") (pin "2") (pinfunction "I1_2") (pintype "input"))
      (node (ref "E45") (pin "10") (pinfunction "O_10") (pintype "output"))
    )
    (net (code "144") (name "Net-(E39B-O)") (class "Default")
      (node (ref "E39") (pin "6") (pinfunction "O_6") (pintype "output"))
      (node (ref "E42") (pin "9") (pinfunction "I_9") (pintype "input"))
    )
    (net (code "145") (name "Net-(E40A-A)") (class "Default")
      (node (ref "E40") (pin "15") (pinfunction "A_15") (pintype "input"))
      (node (ref "E43") (pin "15") (pinfunction "A_15") (pintype "input"))
      (node (ref "E46") (pin "14") (pinfunction "O_14") (pintype "output"))
    )
    (net (code "146") (name "Net-(E40A-B)") (class "Default")
      (node (ref "E40") (pin "14") (pinfunction "B_14") (pintype "input"))
      (node (ref "E43") (pin "14") (pinfunction "B_14") (pintype "input"))
      (node (ref "E46") (pin "3") (pinfunction "O_3") (pintype "output"))
    )
    (net (code "147") (name "Net-(E40A-C)") (class "Default")
      (node (ref "E40") (pin "1") (pinfunction "C_1") (pintype "input"))
      (node (ref "E43") (pin "1") (pinfunction "C_1") (pintype "input"))
      (node (ref "E46") (pin "2") (pinfunction "O_2") (pintype "output"))
    )
    (net (code "148") (name "Net-(E41A-O)") (class "Default")
      (node (ref "E41") (pin "3") (pinfunction "O_3") (pintype "output"))
      (node (ref "E42") (pin "5") (pinfunction "I_5") (pintype "input"))
    )
    (net (code "149") (name "Net-(E42E-I)") (class "Default")
      (node (ref "E42") (pin "11") (pinfunction "I_11") (pintype "input"))
      (node (ref "E45") (pin "4") (pinfunction "O_4") (pintype "output"))
    )
    (net (code "150") (name "Net-(E47A-O)") (class "Default")
      (node (ref "E47") (pin "1") (pinfunction "O_1") (pintype "output"))
      (node (ref "E48") (pin "1") (pinfunction "CLR_1") (pintype "input"))
    )
    (net (code "151") (name "Net-(Q1-B)") (class "Default")
      (node (ref "C58") (pin "1") (pinfunction "1_1") (pintype "passive"))
      (node (ref "C59") (pin "1") (pinfunction "1_1") (pintype "passive"))
      (node (ref "Q1") (pin "2") (pinfunction "B_2") (pintype "passive"))
      (node (ref "R3") (pin "1") (pinfunction "1_1") (pintype "passive"))
    )
    (net (code "152") (name "Net-(Q1-E)") (class "Default")
      (node (ref "C59") (pin "2") (pinfunction "2_2") (pintype "passive"))
      (node (ref "C60") (pin "1") (pinfunction "1_1") (pintype "passive"))
      (node (ref "C61") (pin "1") (pinfunction "1_1") (pintype "passive"))
      (node (ref "Q1") (pin "1") (pinfunction "E_1") (pintype "passive"))
      (node (ref "R4") (pin "1") (pinfunction "1_1") (pintype "passive"))
    )
    (net (code "153") (name "Net-(Q2-E)") (class "Default")
      (node (ref "D4") (pin "A") (pinfunction "A_A") (pintype "passive"))
      (node (ref "Q2") (pin "1") (pinfunction "E_1") (pintype "passive"))
      (node (ref "R8") (pin "1") (pinfunction "1_1") (pintype "passive"))
    )
    (net (code "154") (name "Net-(Q3-B)") (class "Default")
      (node (ref "C63") (pin "1") (pinfunction "1_1") (pintype "passive"))
      (node (ref "Q3") (pin "2") (pinfunction "B_2") (pintype "passive"))
      (node (ref "R13") (pin "2") (pinfunction "2_2") (pintype "passive"))
    )
    (net (code "155") (name "Net-(Q3-C)") (class "Default")
      (node (ref "C63") (pin "2") (pinfunction "2_2") (pintype "passive"))
      (node (ref "D9") (pin "A") (pinfunction "A_A") (pintype "passive"))
      (node (ref "Q3") (pin "3") (pinfunction "C_3") (pintype "passive"))
      (node (ref "R12") (pin "2") (pinfunction "2_2") (pintype "passive"))
    )
    (net (code "156") (name "Net-(R5-Pad2)") (class "Default")
      (node (ref "R5") (pin "2") (pinfunction "2_2") (pintype "passive"))
      (node (ref "R6") (pin "1") (pinfunction "1_1") (pintype "passive"))
      (node (ref "T1") (pin "16") (pinfunction "16_16") (pintype "passive"))
    )
    (net (code "157") (name "Net-(T1-Pad2)") (class "Default")
      (node (ref "T1") (pin "2") (pinfunction "2_2") (pintype "passive"))
      (node (ref "T1") (pin "3") (pinfunction "3_3") (pintype "passive"))
    )
    (net (code "158") (name "Net-(T1-Pad6)") (class "Default")
      (node (ref "T1") (pin "6") (pinfunction "6_6") (pintype "passive"))
      (node (ref "T1") (pin "7") (pinfunction "7_7") (pintype "passive"))
    )
    (net (code "159") (name "Net-(T1-Pad10)") (class "Default")
      (node (ref "T1") (pin "10") (pinfunction "10_10") (pintype "passive"))
      (node (ref "T1") (pin "11") (pinfunction "11_11") (pintype "passive"))
    )
    (net (code "160") (name "Net-(T1-Pad12)") (class "Default")
      (node (ref "T1") (pin "12") (pinfunction "12_12") (pintype "passive"))
      (node (ref "T1") (pin "13") (pinfunction "13_13") (pintype "passive"))
    )
    (net (code "161") (name "Net-(T1-Pad14)") (class "Default")
      (node (ref "T1") (pin "14") (pinfunction "14_14") (pintype "passive"))
      (node (ref "T1") (pin "15") (pinfunction "15_15") (pintype "passive"))
    )
    (net (code "162") (name "POWER_OK") (class "Default")
      (node (ref "E36") (pin "12") (pinfunction "I1_12") (pintype "input"))
      (node (ref "U$2") (pin "BV2") (pinfunction "1_BV2") (pintype "bidirectional"))
    )
    (net (code "163") (name "READER_RUN+") (class "Default")
      (node (ref "C62") (pin "1") (pinfunction "1_1") (pintype "passive"))
      (node (ref "D5") (pin "A") (pinfunction "A_A") (pintype "passive"))
      (node (ref "J1") (pin "PP") (pinfunction "35_PP") (pintype "bidirectional"))
      (node (ref "Q2") (pin "3") (pinfunction "C_3") (pintype "passive"))
    )
    (net (code "164") (name "READER_RUN-") (class "Default")
      (node (ref "J1") (pin "EE") (pinfunction "27_EE") (pintype "bidirectional"))
      (node (ref "R9") (pin "2") (pinfunction "2_2") (pintype "passive"))
    )
    (net (code "165") (name "RTS") (class "Default")
      (node (ref "E32") (pin "8") (pinfunction "O_8") (pintype "output"))
      (node (ref "J1") (pin "V") (pinfunction "18_V") (pintype "bidirectional"))
    )
    (net (code "166") (name "RTSDTR") (class "Default")
      (node (ref "E32") (pin "6") (pinfunction "O_6") (pintype "output"))
      (node (ref "J1") (pin "DD") (pinfunction "26_DD") (pintype "bidirectional"))
    )
    (net (code "167") (name "RX7") (class "Default")
      (node (ref "E1") (pin "11") (pinfunction "I0_11") (pintype "input"))
      (node (ref "E1") (pin "12") (pinfunction "I1_12") (pintype "input"))
      (node (ref "E2") (pin "12") (pinfunction "I1_12") (pintype "input"))
      (node (ref "E6") (pin "5") (pinfunction "Q0_5") (pintype "output"))
      (node (ref "R24") (pin "1") (pinfunction "1_1") (pintype "passive"))
    )
    (net (code "168") (name "RX20MA_DATA") (class "Default")
      (node (ref "C65") (pin "2") (pinfunction "2_2") (pintype "passive"))
      (node (ref "E36") (pin "2") (pinfunction "O_2") (pintype "output"))
      (node (ref "J1") (pin "H") (pinfunction "7_H") (pintype "bidirectional"))
      (node (ref "R19") (pin "2") (pinfunction "2_2") (pintype "passive"))
    )
    (net (code "169") (name "RX_20MA+") (class "Default")
      (node (ref "C64") (pin "1") (pinfunction "1_1") (pintype "passive"))
      (node (ref "J1") (pin "K") (pinfunction "9_K") (pintype "bidirectional"))
      (node (ref "R16") (pin "1") (pinfunction "1_1") (pintype "passive"))
      (node (ref "R22") (pin "1") (pinfunction "1_1") (pintype "passive"))
      (node (ref "U$2") (pin "BB1") (pinfunction "1_BB1") (pintype "bidirectional"))
    )
    (net (code "170") (name "RX_20MA-") (class "Default")
      (node (ref "C64") (pin "2") (pinfunction "2_2") (pintype "passive"))
      (node (ref "J1") (pin "S") (pinfunction "15_S") (pintype "bidirectional"))
      (node (ref "R17") (pin "2") (pinfunction "2_2") (pintype "passive"))
    )
    (net (code "171") (name "RX_ACTIVE") (class "Default")
      (node (ref "E12") (pin "1") (pinfunction "I0_1") (pintype "input"))
      (node (ref "E7") (pin "11") (pinfunction "CLK_11") (pintype "input"))
      (node (ref "E7") (pin "5") (pinfunction "Q_5") (pintype "output"))
      (node (ref "U$2") (pin "AB1") (pinfunction "1_AB1") (pintype "bidirectional"))
    )
    (net (code "172") (name "RX_BOT") (class "Default")
      (node (ref "E10") (pin "12") (pinfunction "Q4_12") (pintype "output"))
      (node (ref "E48") (pin "2") (pinfunction "D_2") (pintype "input"))
      (node (ref "E8") (pin "2") (pinfunction "D_2") (pintype "input"))
    )
    (net (code "173") (name "RX_DATA") (class "Default")
      (node (ref "E21") (pin "12") (pinfunction "O_12") (pintype "output"))
      (node (ref "J1") (pin "M") (pinfunction "11_M") (pintype "bidirectional"))
    )
    (net (code "174") (name "RX_DIV") (class "Default")
      (node (ref "E12") (pin "9") (pinfunction "I0_9") (pintype "input"))
      (node (ref "E3") (pin "5") (pinfunction "Q_5") (pintype "output"))
    )
    (net (code "175") (name "RX_DIV8") (class "Default")
      (node (ref "E12") (pin "2") (pinfunction "I1_2") (pintype "input"))
      (node (ref "E12") (pin "5") (pinfunction "I1_5") (pintype "input"))
      (node (ref "E8") (pin "9") (pinfunction "Q_9") (pintype "output"))
    )
    (net (code "176") (name "RX_LAST") (class "Default")
      (node (ref "E36") (pin "3") (pinfunction "O_3") (pintype "output"))
      (node (ref "E4") (pin "1") (pinfunction "CLR_1") (pintype "input"))
      (node (ref "E4") (pin "13") (pinfunction "CLR_13") (pintype "input"))
      (node (ref "E8") (pin "13") (pinfunction "CLR_13") (pintype "input"))
    )
    (net (code "177") (name "RX_RATE") (class "Default")
      (node (ref "E18") (pin "1") (pinfunction "CKB_1") (pintype "input"))
      (node (ref "E18") (pin "12") (pinfunction "QA_12") (pintype "output"))
      (node (ref "E19") (pin "13") (pinfunction "I2_13") (pintype "input"))
      (node (ref "E3") (pin "10") (pinfunction "PRE_10") (pintype "input"))
      (node (ref "E3") (pin "3") (pinfunction "CLK_3") (pintype "input"))
      (node (ref "H123") (pin "3") (pinfunction "3_3") (pintype "passive"))
    )
    (net (code "178") (name "RX_SEL_L") (class "Default")
      (node (ref "E42") (pin "12") (pinfunction "O_12") (pintype "output"))
      (node (ref "E43") (pin "2") (pinfunction "D_2") (pintype "input"))
    )
    (net (code "179") (name "SELECTED_L") (class "Default")
      (node (ref "E23") (pin "3") (pinfunction "O_3") (pintype "output"))
      (node (ref "E46") (pin "10") (pinfunction "I1_10") (pintype "input"))
      (node (ref "E46") (pin "5") (pinfunction "I1_5") (pintype "input"))
      (node (ref "E46") (pin "6") (pinfunction "I0_6") (pintype "input"))
    )
    (net (code "180") (name "SERIAL_IN") (class "Default")
      (node (ref "E11") (pin "3") (pinfunction "I1_3") (pintype "input"))
      (node (ref "E19") (pin "1") (pinfunction "I0_1") (pintype "input"))
      (node (ref "E21") (pin "9") (pinfunction "I_9") (pintype "input"))
      (node (ref "J1") (pin "E") (pinfunction "5_E") (pintype "bidirectional"))
    )
    (net (code "181") (name "SKIP_L") (class "Default")
      (node (ref "E37") (pin "10") (pinfunction "O_10") (pintype "open_collector"))
      (node (ref "U$2") (pin "CS1") (pinfunction "1_CS1") (pintype "bidirectional"))
    )
    (net (code "182") (name "STP_MARK") (class "Default")
      (node (ref "E25") (pin "1") (pinfunction "I4_1") (pintype "input"))
      (node (ref "J23") (pin "2") (pinfunction "2_2") (pintype "passive"))
      (node (ref "JJ23") (pin "2") (pinfunction "2_2") (pintype "passive"))
    )
    (net (code "183") (name "TKSKP") (class "Default")
      (node (ref "E39") (pin "4") (pinfunction "I3_4") (pintype "input"))
      (node (ref "E39") (pin "5") (pinfunction "I4_5") (pintype "input"))
      (node (ref "E42") (pin "10") (pinfunction "O_10") (pintype "output"))
    )
    (net (code "184") (name "TP3") (class "Default")
      (node (ref "E34") (pin "9") (pinfunction "I0_9") (pintype "input"))
      (node (ref "U$2") (pin "CH2") (pinfunction "1_CH2") (pintype "bidirectional"))
    )
    (net (code "185") (name "TSKP") (class "Default")
      (node (ref "E45") (pin "13") (pinfunction "O_13") (pintype "output"))
      (node (ref "E45") (pin "6") (pinfunction "I1_6") (pintype "input"))
    )
    (net (code "186") (name "TX7") (class "Default")
      (node (ref "E19") (pin "8") (pinfunction "O_8") (pintype "output"))
      (node (ref "E38") (pin "2") (pinfunction "D_2") (pintype "input"))
    )
    (net (code "187") (name "TX8") (class "Default")
      (node (ref "E19") (pin "6") (pinfunction "O_6") (pintype "output"))
      (node (ref "E25") (pin "10") (pinfunction "I1_10") (pintype "input"))
    )
    (net (code "188") (name "TX_20MA+") (class "Default")
      (node (ref "D6") (pin "C") (pinfunction "C_C") (pintype "passive"))
      (node (ref "D9") (pin "C") (pinfunction "C_C") (pintype "passive"))
      (node (ref "J1") (pin "AA") (pinfunction "23_AA") (pintype "bidirectional"))
      (node (ref "R25") (pin "2") (pinfunction "2_2") (pintype "passive"))
    )
    (net (code "189") (name "TX_20MA-") (class "Default")
      (node (ref "J1") (pin "KK") (pinfunction "31_KK") (pintype "bidirectional"))
      (node (ref "R11") (pin "2") (pinfunction "2_2") (pintype "passive"))
    )
    (net (code "190") (name "TX_ACTIVE") (class "Default")
      (node (ref "E20") (pin "11") (pinfunction "CLK_11") (pintype "input"))
      (node (ref "E20") (pin "6") (pinfunction "~{Q}_6") (pintype "output"))
      (node (ref "E25") (pin "9") (pinfunction "I2_9") (pintype "input"))
      (node (ref "E29") (pin "4") (pinfunction "PRE_4") (pintype "input"))
      (node (ref "E35") (pin "10") (pinfunction "I1_10") (pintype "input"))
      (node (ref "U$2") (pin "BA1") (pinfunction "1_BA1") (pintype "bidirectional"))
    )
    (net (code "191") (name "TX_DATA") (class "Default")
      (node (ref "E29") (pin "2") (pinfunction "D_2") (pintype "input"))
      (node (ref "E31") (pin "11") (pinfunction "Q3_11") (pintype "output"))
    )
    (net (code "192") (name "TX_DIV") (class "Default")
      (node (ref "E16") (pin "5") (pinfunction "Q_5") (pintype "output"))
      (node (ref "E25") (pin "4") (pinfunction "I3_4") (pintype "input"))
      (node (ref "E26") (pin "1") (pinfunction "R_1") (pintype "input"))
      (node (ref "E29") (pin "3") (pinfunction "CLK_3") (pintype "input"))
      (node (ref "E35") (pin "9") (pinfunction "I0_9") (pintype "input"))
      (node (ref "E38") (pin "3") (pinfunction "CLK_3") (pintype "input"))
    )
    (net (code "193") (name "TX_RATE") (class "Default")
      (node (ref "E16") (pin "3") (pinfunction "CLK_3") (pintype "input"))
      (node (ref "E20") (pin "13") (pinfunction "CLR_13") (pintype "input"))
      (node (ref "E20") (pin "3") (pinfunction "CLK_3") (pintype "input"))
      (node (ref "E21") (pin "5") (pinfunction "I_5") (pintype "input"))
      (node (ref "H12") (pin "2") (pinfunction "2_2") (pintype "passive"))
      (node (ref "H123") (pin "2") (pinfunction "2_2") (pintype "passive"))
    )
    (net (code "194") (name "TX_SEL_L") (class "Default")
      (node (ref "E33") (pin "10") (pinfunction "O_10") (pintype "open_collector"))
      (node (ref "E40") (pin "2") (pinfunction "D_2") (pintype "input"))
      (node (ref "R26") (pin "1") (pinfunction "1_1") (pintype "passive"))
    )
    (net (code "195") (name "VCC") (class "Default")
      (node (ref "C1") (pin "1") (pinfunction "1_1") (pintype "passive"))
      (node (ref "C10") (pin "1") (pinfunction "1_1") (pintype "passive"))
      (node (ref "C11") (pin "1") (pinfunction "1_1") (pintype "passive"))
      (node (ref "C12") (pin "1") (pinfunction "1_1") (pintype "passive"))
      (node (ref "C13") (pin "1") (pinfunction "1_1") (pintype "passive"))
      (node (ref "C14") (pin "1") (pinfunction "1_1") (pintype "passive"))
      (node (ref "C15") (pin "1") (pinfunction "1_1") (pintype "passive"))
      (node (ref "C16") (pin "1") (pinfunction "1_1") (pintype "passive"))
      (node (ref "C17") (pin "1") (pinfunction "1_1") (pintype "passive"))
      (node (ref "C18") (pin "1") (pinfunction "1_1") (pintype "passive"))
      (node (ref "C19") (pin "1") (pinfunction "1_1") (pintype "passive"))
      (node (ref "C2") (pin "1") (pinfunction "1_1") (pintype "passive"))
      (node (ref "C20") (pin "1") (pinfunction "1_1") (pintype "passive"))
      (node (ref "C21") (pin "1") (pinfunction "1_1") (pintype "passive"))
      (node (ref "C22") (pin "1") (pinfunction "1_1") (pintype "passive"))
      (node (ref "C23") (pin "1") (pinfunction "1_1") (pintype "passive"))
      (node (ref "C24") (pin "1") (pinfunction "1_1") (pintype "passive"))
      (node (ref "C25") (pin "1") (pinfunction "1_1") (pintype "passive"))
      (node (ref "C26") (pin "1") (pinfunction "1_1") (pintype "passive"))
      (node (ref "C27") (pin "1") (pinfunction "1_1") (pintype "passive"))
      (node (ref "C28") (pin "1") (pinfunction "1_1") (pintype "passive"))
      (node (ref "C29") (pin "1") (pinfunction "1_1") (pintype "passive"))
      (node (ref "C3") (pin "1") (pinfunction "1_1") (pintype "passive"))
      (node (ref "C30") (pin "1") (pinfunction "1_1") (pintype "passive"))
      (node (ref "C31") (pin "1") (pinfunction "1_1") (pintype "passive"))
      (node (ref "C33") (pin "1") (pinfunction "1_1") (pintype "passive"))
      (node (ref "C34") (pin "1") (pinfunction "1_1") (pintype "passive"))
      (node (ref "C35") (pin "1") (pinfunction "1_1") (pintype "passive"))
      (node (ref "C36") (pin "1") (pinfunction "1_1") (pintype "passive"))
      (node (ref "C37") (pin "1") (pinfunction "1_1") (pintype "passive"))
      (node (ref "C38") (pin "1") (pinfunction "1_1") (pintype "passive"))
      (node (ref "C39") (pin "1") (pinfunction "1_1") (pintype "passive"))
      (node (ref "C4") (pin "1") (pinfunction "1_1") (pintype "passive"))
      (node (ref "C40") (pin "1") (pinfunction "1_1") (pintype "passive"))
      (node (ref "C41") (pin "1") (pinfunction "1_1") (pintype "passive"))
      (node (ref "C42") (pin "1") (pinfunction "1_1") (pintype "passive"))
      (node (ref "C43") (pin "1") (pinfunction "1_1") (pintype "passive"))
      (node (ref "C44") (pin "1") (pinfunction "1_1") (pintype "passive"))
      (node (ref "C45") (pin "1") (pinfunction "1_1") (pintype "passive"))
      (node (ref "C46") (pin "1") (pinfunction "1_1") (pintype "passive"))
      (node (ref "C47") (pin "1") (pinfunction "1_1") (pintype "passive"))
      (node (ref "C48") (pin "1") (pinfunction "1_1") (pintype "passive"))
      (node (ref "C5") (pin "1") (pinfunction "1_1") (pintype "passive"))
      (node (ref "C51") (pin "+") (pinfunction "+_+") (pintype "passive"))
      (node (ref "C52") (pin "+") (pinfunction "+_+") (pintype "passive"))
      (node (ref "C53") (pin "+") (pinfunction "+_+") (pintype "passive"))
      (node (ref "C56") (pin "+") (pinfunction "+_+") (pintype "passive"))
      (node (ref "C57") (pin "1") (pinfunction "1_1") (pintype "passive"))
      (node (ref "C6") (pin "1") (pinfunction "1_1") (pintype "passive"))
      (node (ref "C7") (pin "1") (pinfunction "1_1") (pintype "passive"))
      (node (ref "C8") (pin "1") (pinfunction "1_1") (pintype "passive"))
      (node (ref "C9") (pin "1") (pinfunction "1_1") (pintype "passive"))
      (node (ref "D7") (pin "C") (pinfunction "C_C") (pintype "passive"))
      (node (ref "Q1") (pin "3") (pinfunction "C_3") (pintype "passive"))
      (node (ref "Q3") (pin "1") (pinfunction "E_1") (pintype "passive"))
      (node (ref "R1") (pin "2") (pinfunction "2_2") (pintype "passive"))
      (node (ref "R10") (pin "2") (pinfunction "2_2") (pintype "passive"))
      (node (ref "R14") (pin "2") (pinfunction "2_2") (pintype "passive"))
      (node (ref "R15") (pin "2") (pinfunction "2_2") (pintype "passive"))
      (node (ref "R16") (pin "2") (pinfunction "2_2") (pintype "passive"))
      (node (ref "R21") (pin "2") (pinfunction "2_2") (pintype "passive"))
      (node (ref "R24") (pin "2") (pinfunction "2_2") (pintype "passive"))
      (node (ref "R26") (pin "2") (pinfunction "2_2") (pintype "passive"))
      (node (ref "R3") (pin "2") (pinfunction "2_2") (pintype "passive"))
      (node (ref "R7") (pin "2") (pinfunction "2_2") (pintype "passive"))
      (node (ref "R8") (pin "2") (pinfunction "2_2") (pintype "passive"))
      (node (ref "U$2") (pin "AA2") (pinfunction "1_AA2") (pintype "bidirectional"))
      (node (ref "U$2") (pin "BA2") (pinfunction "1_BA2") (pintype "bidirectional"))
      (node (ref "U$2") (pin "CA2") (pinfunction "1_CA2") (pintype "bidirectional"))
    )
    (net (code "196") (name "unconnected-(E3B-Q-Pad9)") (class "Default")
      (node (ref "E3") (pin "9") (pinfunction "Q_9") (pintype "output"))
    )
    (net (code "197") (name "unconnected-(E4A-Q-Pad5)") (class "Default")
      (node (ref "E4") (pin "5") (pinfunction "Q_5") (pintype "output"))
    )
    (net (code "198") (name "unconnected-(E4B-Q-Pad9)") (class "Default")
      (node (ref "E4") (pin "9") (pinfunction "Q_9") (pintype "output"))
    )
    (net (code "199") (name "unconnected-(E5A-QB-Pad9)") (class "Default")
      (node (ref "E5") (pin "9") (pinfunction "QB_9") (pintype "output"))
    )
    (net (code "200") (name "unconnected-(E5A-QC-Pad8)") (class "Default")
      (node (ref "E5") (pin "8") (pinfunction "QC_8") (pintype "output"))
    )
    (net (code "201") (name "unconnected-(E6A-Q4-Pad12)") (class "Default")
      (node (ref "E6") (pin "12") (pinfunction "Q4_12") (pintype "output"))
    )
    (net (code "202") (name "unconnected-(E7B-~{Q}-Pad8)") (class "Default")
      (node (ref "E7") (pin "8") (pinfunction "~{Q}_8") (pintype "output"))
    )
    (net (code "203") (name "unconnected-(E16B-Q-Pad9)") (class "Default")
      (node (ref "E16") (pin "9") (pinfunction "Q_9") (pintype "output"))
    )
    (net (code "204") (name "unconnected-(E18A-QB-Pad9)") (class "Default")
      (node (ref "E18") (pin "9") (pinfunction "QB_9") (pintype "output"))
    )
    (net (code "205") (name "unconnected-(E18A-QC-Pad8)") (class "Default")
      (node (ref "E18") (pin "8") (pinfunction "QC_8") (pintype "output"))
    )
    (net (code "206") (name "unconnected-(E20B-Q-Pad9)") (class "Default")
      (node (ref "E20") (pin "9") (pinfunction "Q_9") (pintype "output"))
    )
    (net (code "207") (name "unconnected-(E22A-BO-Pad13)") (class "Default")
      (node (ref "E22") (pin "13") (pinfunction "BO_13") (pintype "output"))
    )
    (net (code "208") (name "unconnected-(E22A-CO-Pad12)") (class "Default")
      (node (ref "E22") (pin "12") (pinfunction "CO_12") (pintype "output"))
    )
    (net (code "209") (name "unconnected-(E22A-QA-Pad3)") (class "Default")
      (node (ref "E22") (pin "3") (pinfunction "QA_3") (pintype "output"))
    )
    (net (code "210") (name "unconnected-(E22A-QB-Pad2)") (class "Default")
      (node (ref "E22") (pin "2") (pinfunction "QB_2") (pintype "output"))
    )
    (net (code "211") (name "unconnected-(E22A-QC-Pad6)") (class "Default")
      (node (ref "E22") (pin "6") (pinfunction "QC_6") (pintype "output"))
    )
    (net (code "212") (name "unconnected-(E25A-I5-Pad12)") (class "Default")
      (node (ref "E25") (pin "12") (pinfunction "I5_12") (pintype "passive"))
    )
    (net (code "213") (name "unconnected-(E25A-I6-Pad11)") (class "Default")
      (node (ref "E25") (pin "11") (pinfunction "I6_11") (pintype "passive"))
    )
    (net (code "214") (name "unconnected-(E26A-I0-Pad3)") (class "Default")
      (node (ref "E26") (pin "3") (pinfunction "I0_3") (pintype "input"))
    )
    (net (code "215") (name "unconnected-(E26A-I1-Pad2)") (class "Default")
      (node (ref "E26") (pin "2") (pinfunction "I1_2") (pintype "input"))
    )
    (net (code "216") (name "unconnected-(E26A-I2-Pad15)") (class "Default")
      (node (ref "E26") (pin "15") (pinfunction "I2_15") (pintype "input"))
    )
    (net (code "217") (name "unconnected-(E26A-I3-Pad14)") (class "Default")
      (node (ref "E26") (pin "14") (pinfunction "I3_14") (pintype "input"))
    )
    (net (code "218") (name "unconnected-(E26A-Q1-Pad7)") (class "Default")
      (node (ref "E26") (pin "7") (pinfunction "Q1_7") (pintype "output"))
    )
    (net (code "219") (name "unconnected-(E26A-Q3-Pad11)") (class "Default")
      (node (ref "E26") (pin "11") (pinfunction "Q3_11") (pintype "output"))
    )
    (net (code "220") (name "unconnected-(E26A-Q4-Pad12)") (class "Default")
      (node (ref "E26") (pin "12") (pinfunction "Q4_12") (pintype "output"))
    )
    (net (code "221") (name "unconnected-(E28A-Q4-Pad12)") (class "Default")
      (node (ref "E28") (pin "12") (pinfunction "Q4_12") (pintype "output"))
    )
    (net (code "222") (name "unconnected-(E29B-~{Q}-Pad8)") (class "Default")
      (node (ref "E29") (pin "8") (pinfunction "~{Q}_8") (pintype "output"))
    )
    (net (code "223") (name "unconnected-(E31A-Q4-Pad12)") (class "Default")
      (node (ref "E31") (pin "12") (pinfunction "Q4_12") (pintype "output"))
    )
    (net (code "224") (name "unconnected-(E38A-~{Q}-Pad6)") (class "Default")
      (node (ref "E38") (pin "6") (pinfunction "~{Q}_6") (pintype "output"))
    )
    (net (code "225") (name "unconnected-(E39A-I5-Pad12)") (class "Default")
      (node (ref "E39") (pin "12") (pinfunction "I5_12") (pintype "passive"))
    )
    (net (code "226") (name "unconnected-(E39A-I6-Pad11)") (class "Default")
      (node (ref "E39") (pin "11") (pinfunction "I6_11") (pintype "passive"))
    )
    (net (code "227") (name "unconnected-(E40A-3-Pad10)") (class "Default")
      (node (ref "E40") (pin "10") (pinfunction "3_10") (pintype "output"))
    )
    (net (code "228") (name "unconnected-(E40A-7-Pad5)") (class "Default")
      (node (ref "E40") (pin "5") (pinfunction "7_5") (pintype "output"))
    )
    (net (code "229") (name "unconnected-(E40A-8-Pad6)") (class "Default")
      (node (ref "E40") (pin "6") (pinfunction "8_6") (pintype "output"))
    )
    (net (code "230") (name "unconnected-(E40A-9-Pad7)") (class "Default")
      (node (ref "E40") (pin "7") (pinfunction "9_7") (pintype "output"))
    )
    (net (code "231") (name "unconnected-(E43A-3-Pad10)") (class "Default")
      (node (ref "E43") (pin "10") (pinfunction "3_10") (pintype "output"))
    )
    (net (code "232") (name "unconnected-(E43A-7-Pad5)") (class "Default")
      (node (ref "E43") (pin "5") (pinfunction "7_5") (pintype "output"))
    )
    (net (code "233") (name "unconnected-(E43A-8-Pad6)") (class "Default")
      (node (ref "E43") (pin "6") (pinfunction "8_6") (pintype "output"))
    )
    (net (code "234") (name "unconnected-(E43A-9-Pad7)") (class "Default")
      (node (ref "E43") (pin "7") (pinfunction "9_7") (pintype "output"))
    )
    (net (code "235") (name "unconnected-(E48A-Q-Pad5)") (class "Default")
      (node (ref "E48") (pin "5") (pinfunction "Q_5") (pintype "output"))
    )
    (net (code "236") (name "unconnected-(E48B-~{Q}-Pad8)") (class "Default")
      (node (ref "E48") (pin "8") (pinfunction "~{Q}_8") (pintype "output"))
    )
    (net (code "237") (name "unconnected-(J1-4-PadD)") (class "Default")
      (node (ref "J1") (pin "D") (pinfunction "4_D") (pintype "bidirectional"))
    )
    (net (code "238") (name "unconnected-(J1-10-PadL)") (class "Default")
      (node (ref "J1") (pin "L") (pinfunction "10_L") (pintype "bidirectional"))
    )
    (net (code "239") (name "unconnected-(J1-12-PadN)") (class "Default")
      (node (ref "J1") (pin "N") (pinfunction "12_N") (pintype "bidirectional"))
    )
    (net (code "240") (name "unconnected-(J1-13-PadP)") (class "Default")
      (node (ref "J1") (pin "P") (pinfunction "13_P") (pintype "bidirectional"))
    )
    (net (code "241") (name "unconnected-(J1-14-PadR)") (class "Default")
      (node (ref "J1") (pin "R") (pinfunction "14_R") (pintype "bidirectional"))
    )
    (net (code "242") (name "unconnected-(J1-16-PadT)") (class "Default")
      (node (ref "J1") (pin "T") (pinfunction "16_T") (pintype "bidirectional"))
    )
    (net (code "243") (name "unconnected-(J1-17-PadU)") (class "Default")
      (node (ref "J1") (pin "U") (pinfunction "17_U") (pintype "bidirectional"))
    )
    (net (code "244") (name "unconnected-(J1-19-PadW)") (class "Default")
      (node (ref "J1") (pin "W") (pinfunction "19_W") (pintype "bidirectional"))
    )
    (net (code "245") (name "unconnected-(J1-20-PadX)") (class "Default")
      (node (ref "J1") (pin "X") (pinfunction "20_X") (pintype "bidirectional"))
    )
    (net (code "246") (name "unconnected-(J1-21-PadY)") (class "Default")
      (node (ref "J1") (pin "Y") (pinfunction "21_Y") (pintype "bidirectional"))
    )
    (net (code "247") (name "unconnected-(J1-22-PadZ)") (class "Default")
      (node (ref "J1") (pin "Z") (pinfunction "22_Z") (pintype "bidirectional"))
    )
    (net (code "248") (name "unconnected-(J1-24-PadBB)") (class "Default")
      (node (ref "J1") (pin "BB") (pinfunction "24_BB") (pintype "bidirectional"))
    )
    (net (code "249") (name "unconnected-(J1-25-PadCC)") (class "Default")
      (node (ref "J1") (pin "CC") (pinfunction "25_CC") (pintype "bidirectional"))
    )
    (net (code "250") (name "unconnected-(J1-28-PadFF)") (class "Default")
      (node (ref "J1") (pin "FF") (pinfunction "28_FF") (pintype "bidirectional"))
    )
    (net (code "251") (name "unconnected-(J1-29-PadHH)") (class "Default")
      (node (ref "J1") (pin "HH") (pinfunction "29_HH") (pintype "bidirectional"))
    )
    (net (code "252") (name "unconnected-(J1-30-PadJJ)") (class "Default")
      (node (ref "J1") (pin "JJ") (pinfunction "30_JJ") (pintype "bidirectional"))
    )
    (net (code "253") (name "unconnected-(J1-32-PadLL)") (class "Default")
      (node (ref "J1") (pin "LL") (pinfunction "32_LL") (pintype "bidirectional"))
    )
    (net (code "254") (name "unconnected-(J1-33-PadMM)") (class "Default")
      (node (ref "J1") (pin "MM") (pinfunction "33_MM") (pintype "bidirectional"))
    )
    (net (code "255") (name "unconnected-(J1-34-PadNN)") (class "Default")
      (node (ref "J1") (pin "NN") (pinfunction "34_NN") (pintype "bidirectional"))
    )
    (net (code "256") (name "unconnected-(J1-36-PadRR)") (class "Default")
      (node (ref "J1") (pin "RR") (pinfunction "36_RR") (pintype "bidirectional"))
    )
    (net (code "257") (name "unconnected-(J1-37-PadSS)") (class "Default")
      (node (ref "J1") (pin "SS") (pinfunction "37_SS") (pintype "bidirectional"))
    )
    (net (code "258") (name "unconnected-(J1-38-PadTT)") (class "Default")
      (node (ref "J1") (pin "TT") (pinfunction "38_TT") (pintype "bidirectional"))
    )
    (net (code "259") (name "~{CKKCC}") (class "Default")
      (node (ref "E35") (pin "4") (pinfunction "I0_4") (pintype "input"))
      (node (ref "E44") (pin "11") (pinfunction "O_11") (pintype "output"))
      (node (ref "E48") (pin "13") (pinfunction "CLR_13") (pintype "input"))
    )
    (net (code "260") (name "~{CKTFL}") (class "Default")
      (node (ref "E38") (pin "1") (pinfunction "CLR_1") (pintype "input"))
      (node (ref "E42") (pin "2") (pinfunction "O_2") (pintype "output"))
    )
    (net (code "261") (name "~{DOTPC}") (class "Default")
      (node (ref "E27") (pin "10") (pinfunction "I1_10") (pintype "input"))
      (node (ref "E27") (pin "11") (pinfunction "I0_11") (pintype "input"))
      (node (ref "E27") (pin "5") (pinfunction "I1_5") (pintype "input"))
      (node (ref "E27") (pin "6") (pinfunction "I0_6") (pintype "input"))
      (node (ref "E28") (pin "13") (pinfunction "S_13") (pintype "input"))
      (node (ref "E30") (pin "10") (pinfunction "I1_10") (pintype "input"))
      (node (ref "E30") (pin "11") (pinfunction "I0_11") (pintype "input"))
      (node (ref "E30") (pin "5") (pinfunction "I1_5") (pintype "input"))
      (node (ref "E30") (pin "6") (pinfunction "I0_6") (pintype "input"))
      (node (ref "E31") (pin "13") (pinfunction "S_13") (pintype "input"))
      (node (ref "E35") (pin "3") (pinfunction "O_3") (pintype "output"))
      (node (ref "R10") (pin "1") (pinfunction "1_1") (pintype "passive"))
    )
    (net (code "262") (name "~{INIT}") (class "Default")
      (node (ref "E16") (pin "13") (pinfunction "CLR_13") (pintype "input"))
      (node (ref "E16") (pin "4") (pinfunction "PRE_4") (pintype "input"))
      (node (ref "E29") (pin "13") (pinfunction "CLR_13") (pintype "input"))
      (node (ref "E46") (pin "13") (pinfunction "O_13") (pintype "output"))
      (node (ref "E48") (pin "10") (pinfunction "PRE_10") (pintype "input"))
    )
    (net (code "263") (name "~{INT_ENAB}") (class "Default")
      (node (ref "E38") (pin "9") (pinfunction "Q_9") (pintype "output"))
      (node (ref "E45") (pin "9") (pinfunction "I1_9") (pintype "input"))
    )
    (net (code "264") (name "~{KCC}") (class "Default")
      (node (ref "E43") (pin "11") (pinfunction "2_11") (pintype "output"))
      (node (ref "E44") (pin "10") (pinfunction "I1_10") (pintype "input"))
    )
    (net (code "265") (name "~{KCF}") (class "Default")
      (node (ref "E43") (pin "13") (pinfunction "0_13") (pintype "output"))
      (node (ref "E47") (pin "6") (pinfunction "I1_6") (pintype "input"))
    )
    (net (code "266") (name "~{KIE}") (class "Default")
      (node (ref "E43") (pin "3") (pinfunction "5_3") (pintype "output"))
      (node (ref "E47") (pin "8") (pinfunction "I0_8") (pintype "input"))
    )
    (net (code "267") (name "~{KRB}") (class "Default")
      (node (ref "E43") (pin "4") (pinfunction "6_4") (pintype "output"))
      (node (ref "E44") (pin "4") (pinfunction "I0_4") (pintype "input"))
      (node (ref "E44") (pin "9") (pinfunction "I0_9") (pintype "input"))
    )
    (net (code "268") (name "~{KRS}") (class "Default")
      (node (ref "E43") (pin "9") (pinfunction "4_9") (pintype "output"))
      (node (ref "E44") (pin "5") (pinfunction "I1_5") (pintype "input"))
    )
    (net (code "269") (name "~{KSF}") (class "Default")
      (node (ref "E43") (pin "12") (pinfunction "1_12") (pintype "output"))
      (node (ref "E47") (pin "11") (pinfunction "I0_11") (pintype "input"))
    )
    (net (code "270") (name "~{LAST_UNIT}") (class "Default")
      (node (ref "E12") (pin "12") (pinfunction "I0_12") (pintype "input"))
      (node (ref "E8") (pin "6") (pinfunction "~{Q}_6") (pintype "output"))
    )
    (net (code "271") (name "~{LINE}") (class "Default")
      (node (ref "E29") (pin "6") (pinfunction "~{Q}_6") (pintype "output"))
      (node (ref "R13") (pin "1") (pinfunction "1_1") (pintype "passive"))
      (node (ref "R14") (pin "1") (pinfunction "1_1") (pintype "passive"))
    )
    (net (code "272") (name "~{P_PULSE}") (class "Default")
      (node (ref "E10") (pin "13") (pinfunction "S_13") (pintype "input"))
      (node (ref "E11") (pin "8") (pinfunction "I0_8") (pintype "input"))
      (node (ref "E6") (pin "13") (pinfunction "S_13") (pintype "input"))
      (node (ref "E7") (pin "9") (pinfunction "Q_9") (pintype "output"))
    )
    (net (code "273") (name "~{RFLG}") (class "Default")
      (node (ref "E44") (pin "1") (pinfunction "I0_1") (pintype "input"))
      (node (ref "E47") (pin "12") (pinfunction "I1_12") (pintype "input"))
      (node (ref "E48") (pin "6") (pinfunction "~{Q}_6") (pintype "output"))
    )
    (net (code "274") (name "~{RX_ACTIVE8}") (class "Default")
      (node (ref "E11") (pin "11") (pinfunction "I0_11") (pintype "input"))
      (node (ref "E11") (pin "12") (pinfunction "I1_12") (pintype "input"))
      (node (ref "E12") (pin "3") (pinfunction "O_3") (pintype "output"))
      (node (ref "E16") (pin "11") (pinfunction "CLK_11") (pintype "input"))
      (node (ref "E39") (pin "1") (pinfunction "I4_1") (pintype "input"))
    )
    (net (code "275") (name "~{RX_ACTIVE}") (class "Default")
      (node (ref "E12") (pin "13") (pinfunction "I1_13") (pintype "input"))
      (node (ref "E12") (pin "4") (pinfunction "I0_4") (pintype "input"))
      (node (ref "E7") (pin "6") (pinfunction "~{Q}_6") (pintype "output"))
    )
    (net (code "276") (name "~{RX_AGAIN}") (class "Default")
      (node (ref "E16") (pin "10") (pinfunction "PRE_10") (pintype "input"))
      (node (ref "E19") (pin "12") (pinfunction "O_12") (pintype "output"))
      (node (ref "E7") (pin "4") (pinfunction "PRE_4") (pintype "input"))
    )
    (net (code "277") (name "~{RX_DIV2}") (class "Default")
      (node (ref "E11") (pin "9") (pinfunction "I1_9") (pintype "input"))
      (node (ref "E4") (pin "11") (pinfunction "CLK_11") (pintype "input"))
      (node (ref "E4") (pin "2") (pinfunction "D_2") (pintype "input"))
      (node (ref "E4") (pin "6") (pinfunction "~{Q}_6") (pintype "output"))
    )
    (net (code "278") (name "~{RX_DIV4}") (class "Default")
      (node (ref "E4") (pin "12") (pinfunction "D_12") (pintype "input"))
      (node (ref "E4") (pin "8") (pinfunction "~{Q}_8") (pintype "output"))
      (node (ref "E7") (pin "10") (pinfunction "PRE_10") (pintype "input"))
      (node (ref "E8") (pin "11") (pinfunction "CLK_11") (pintype "input"))
    )
    (net (code "279") (name "~{RX_DIV}") (class "Default")
      (node (ref "E3") (pin "6") (pinfunction "~{Q}_6") (pintype "output"))
      (node (ref "E4") (pin "3") (pinfunction "CLK_3") (pintype "input"))
    )
    (net (code "280") (name "~{RX_LAST}") (class "Default")
      (node (ref "E12") (pin "10") (pinfunction "I1_10") (pintype "input"))
      (node (ref "E12") (pin "11") (pinfunction "O_11") (pintype "output"))
      (node (ref "E21") (pin "11") (pinfunction "I_11") (pintype "input"))
      (node (ref "E36") (pin "4") (pinfunction "I0_4") (pintype "input"))
      (node (ref "E36") (pin "5") (pinfunction "I1_5") (pintype "input"))
      (node (ref "R15") (pin "1") (pinfunction "1_1") (pintype "passive"))
    )
    (net (code "281") (name "~{R_RUN}") (class "Default")
      (node (ref "E32") (pin "10") (pinfunction "I1_10") (pintype "input"))
      (node (ref "E32") (pin "9") (pinfunction "I0_9") (pintype "input"))
      (node (ref "E48") (pin "9") (pinfunction "Q_9") (pintype "output"))
      (node (ref "Q2") (pin "2") (pinfunction "B_2") (pintype "passive"))
      (node (ref "U$2") (pin "DB1") (pinfunction "1_DB1") (pintype "bidirectional"))
    )
    (net (code "282") (name "~{SPIKE_DET}") (class "Default")
      (node (ref "E11") (pin "2") (pinfunction "I0_2") (pintype "input"))
      (node (ref "E16") (pin "8") (pinfunction "~{Q}_8") (pintype "output"))
    )
    (net (code "283") (name "~{START}") (class "Default")
      (node (ref "E20") (pin "8") (pinfunction "~{Q}_8") (pintype "output"))
      (node (ref "E29") (pin "1") (pinfunction "CLR_1") (pintype "input"))
    )
    (net (code "284") (name "~{TCF}") (class "Default")
      (node (ref "E40") (pin "11") (pinfunction "2_11") (pintype "output"))
      (node (ref "E41") (pin "10") (pinfunction "I1_10") (pintype "input"))
    )
    (net (code "285") (name "~{TFLG}") (class "Default")
      (node (ref "E38") (pin "5") (pinfunction "Q_5") (pintype "output"))
      (node (ref "E44") (pin "2") (pinfunction "I1_2") (pintype "input"))
      (node (ref "E45") (pin "11") (pinfunction "I0_11") (pintype "input"))
    )
    (net (code "286") (name "~{TFL}") (class "Default")
      (node (ref "E40") (pin "13") (pinfunction "0_13") (pintype "output"))
      (node (ref "E45") (pin "2") (pinfunction "I0_2") (pintype "input"))
    )
    (net (code "287") (name "~{TLS}") (class "Default")
      (node (ref "E40") (pin "4") (pinfunction "6_4") (pintype "output"))
      (node (ref "E41") (pin "4") (pinfunction "I0_4") (pintype "input"))
      (node (ref "E41") (pin "9") (pinfunction "I0_9") (pintype "input"))
    )
    (net (code "288") (name "~{TP3}") (class "Default")
      (node (ref "E42") (pin "4") (pinfunction "O_4") (pintype "output"))
      (node (ref "E45") (pin "3") (pinfunction "I1_3") (pintype "input"))
      (node (ref "E47") (pin "5") (pinfunction "I0_5") (pintype "input"))
      (node (ref "E47") (pin "9") (pinfunction "I1_9") (pintype "input"))
    )
    (net (code "289") (name "~{TPC}") (class "Default")
      (node (ref "E40") (pin "9") (pinfunction "4_9") (pintype "output"))
      (node (ref "E41") (pin "5") (pinfunction "I1_5") (pintype "input"))
    )
    (net (code "290") (name "~{TSF}") (class "Default")
      (node (ref "E40") (pin "12") (pinfunction "1_12") (pintype "output"))
      (node (ref "E45") (pin "12") (pinfunction "I1_12") (pintype "input"))
    )
    (net (code "291") (name "~{TSK}") (class "Default")
      (node (ref "E40") (pin "3") (pinfunction "5_3") (pintype "output"))
      (node (ref "E45") (pin "8") (pinfunction "I0_8") (pintype "input"))
    )
    (net (code "292") (name "~{TX_ACTIVE}") (class "Default")
      (node (ref "E20") (pin "5") (pinfunction "Q_5") (pintype "output"))
      (node (ref "E26") (pin "4") (pinfunction "D_4") (pintype "input"))
    )
    (net (code "293") (name "~{TX_DIV}") (class "Default")
      (node (ref "DL1") (pin "1") (pinfunction "1_1") (pintype "passive"))
      (node (ref "E16") (pin "6") (pinfunction "~{Q}_6") (pintype "output"))
      (node (ref "E19") (pin "4") (pinfunction "I1_4") (pintype "input"))
      (node (ref "R21") (pin "1") (pinfunction "1_1") (pintype "passive"))
    )
    (net (code "294") (name "~{TX_SHIFT}") (class "Default")
      (node (ref "E21") (pin "3") (pinfunction "I_3") (pintype "input"))
      (node (ref "E25") (pin "6") (pinfunction "O_6") (pintype "output"))
      (node (ref "E28") (pin "6") (pinfunction "C_6") (pintype "input"))
      (node (ref "E31") (pin "6") (pinfunction "C_6") (pintype "input"))
    )
  )
)
